# Interface.net
KiCad netlist of a schematic drawn in Altium Designer
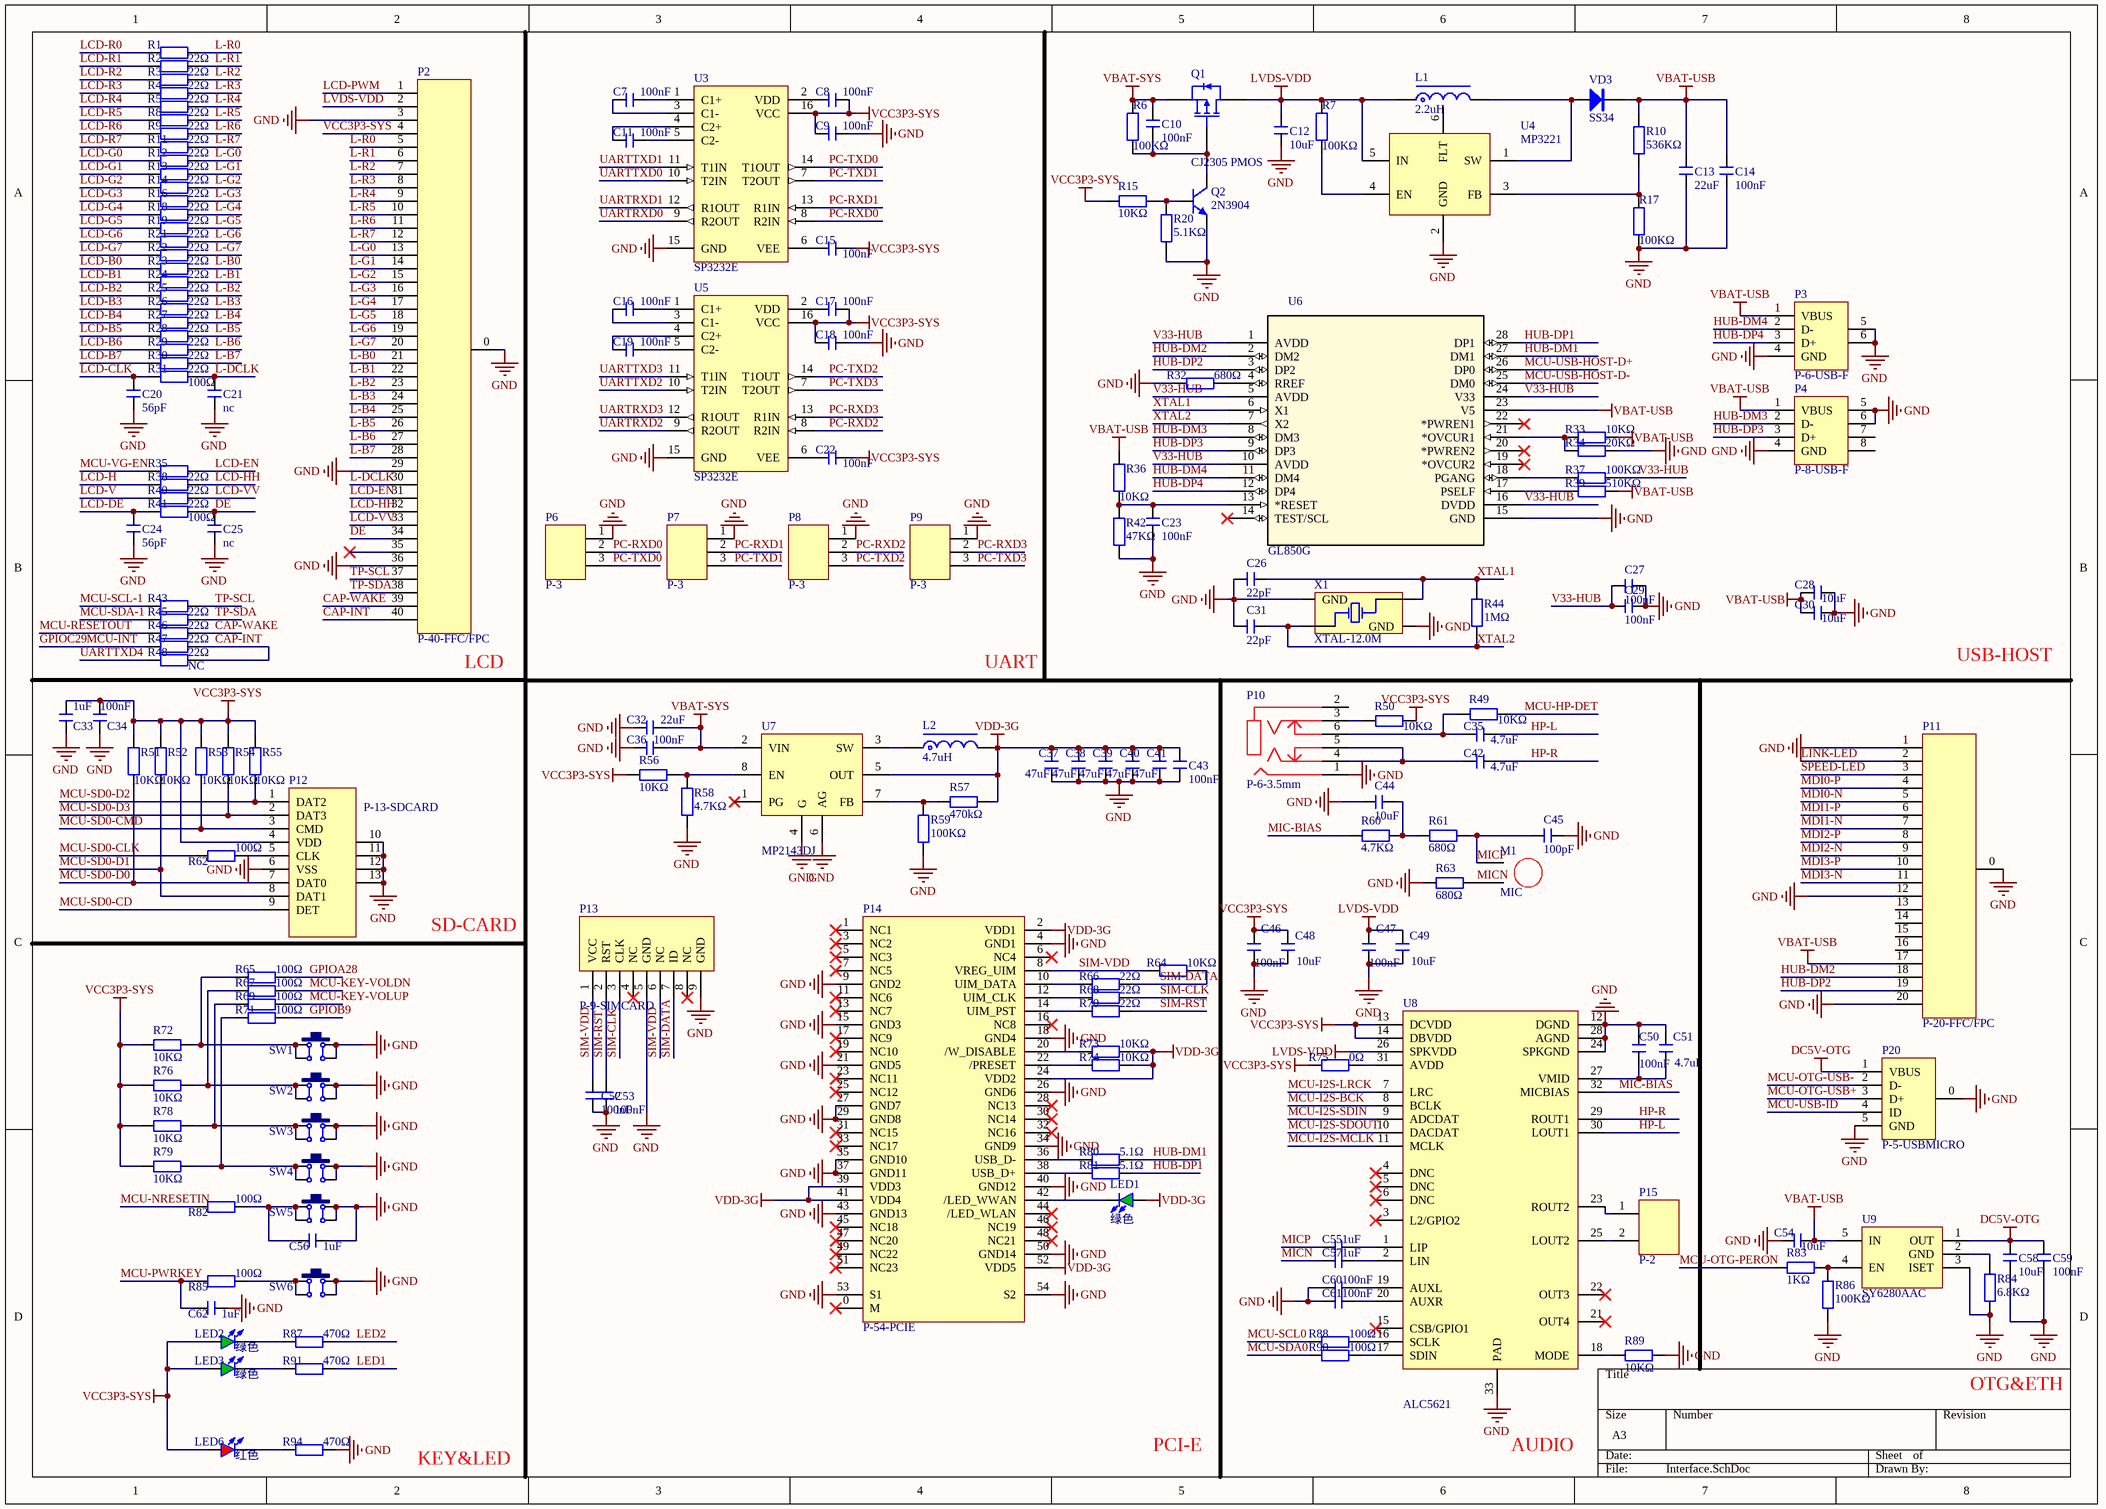
[diagram p0: Interface.SchDoc]

(export (version "E")
  (design (tool "Eeschema 10.0.6"))
  (components
    (comp (ref "C7")
      (value "100nF")
      (footprint "C 0402")
      (description "无极性贴片电容")
      (fields (field (name "版权归属") "源创客"))
      (libsource (lib "ZZF_Library") (part "C 100nF"))
    )
    (comp (ref "C8")
      (value "100nF")
      (footprint "C 0402")
      (description "无极性贴片电容")
      (fields (field (name "版权归属") "源创客"))
      (libsource (lib "ZZF_Library") (part "C 100nF"))
    )
    (comp (ref "C9")
      (value "100nF")
      (footprint "C 0402")
      (description "无极性贴片电容")
      (fields (field (name "版权归属") "源创客"))
      (libsource (lib "ZZF_Library") (part "C 100nF"))
    )
    (comp (ref "C10")
      (value "100nF")
      (footprint "C 0402")
      (description "无极性贴片电容")
      (fields (field (name "版权归属") "源创客"))
      (libsource (lib "ZZF_Library") (part "C 100nF"))
    )
    (comp (ref "C11")
      (value "100nF")
      (footprint "C 0402")
      (description "无极性贴片电容")
      (fields (field (name "版权归属") "源创客"))
      (libsource (lib "ZZF_Library") (part "C 100nF"))
    )
    (comp (ref "C12")
      (value "10uF")
      (footprint "C 0402")
      (description "无极性贴片电容")
      (fields (field (name "版权归属") "源创客"))
      (libsource (lib "ZZF_Library") (part "C 10uF"))
    )
    (comp (ref "C13")
      (value "22uF")
      (footprint "C 0805")
      (description "无极性贴片电容")
      (fields (field (name "版权归属") "源创客"))
      (libsource (lib "ZZF_Library") (part "C 22uF"))
    )
    (comp (ref "C14")
      (value "100nF")
      (footprint "C 0402")
      (description "无极性贴片电容")
      (fields (field (name "版权归属") "源创客"))
      (libsource (lib "ZZF_Library") (part "C 100nF"))
    )
    (comp (ref "C15")
      (value "100nF")
      (footprint "C 0402")
      (description "无极性贴片电容")
      (fields (field (name "版权归属") "源创客"))
      (libsource (lib "ZZF_Library") (part "C 100nF"))
    )
    (comp (ref "C16")
      (value "100nF")
      (footprint "C 0402")
      (description "无极性贴片电容")
      (fields (field (name "版权归属") "源创客"))
      (libsource (lib "ZZF_Library") (part "C 100nF"))
    )
    (comp (ref "C17")
      (value "100nF")
      (footprint "C 0402")
      (description "无极性贴片电容")
      (fields (field (name "版权归属") "源创客"))
      (libsource (lib "ZZF_Library") (part "C 100nF"))
    )
    (comp (ref "C18")
      (value "100nF")
      (footprint "C 0402")
      (description "无极性贴片电容")
      (fields (field (name "版权归属") "源创客"))
      (libsource (lib "ZZF_Library") (part "C 100nF"))
    )
    (comp (ref "C19")
      (value "100nF")
      (footprint "C 0402")
      (description "无极性贴片电容")
      (fields (field (name "版权归属") "源创客"))
      (libsource (lib "ZZF_Library") (part "C 100nF"))
    )
    (comp (ref "C20")
      (value "56pF")
      (footprint "C 0402")
      (description "无极性贴片电容")
      (fields (field (name "版权归属") "源创客"))
      (libsource (lib "ZZF_Library") (part "C 56pF"))
    )
    (comp (ref "C21")
      (value "nc")
      (footprint "C 0402")
      (description "无极性贴片电容")
      (fields (field (name "版权归属") "源创客"))
      (libsource (lib "ZZF_Library") (part "C 56pF"))
    )
    (comp (ref "C22")
      (value "100nF")
      (footprint "C 0402")
      (description "无极性贴片电容")
      (fields (field (name "版权归属") "源创客"))
      (libsource (lib "ZZF_Library") (part "C 100nF"))
    )
    (comp (ref "C23")
      (value "100nF")
      (footprint "C 0402")
      (description "无极性贴片电容")
      (fields (field (name "版权归属") "源创客"))
      (libsource (lib "ZZF_Library") (part "C 100nF"))
    )
    (comp (ref "C24")
      (value "56pF")
      (footprint "C 0402")
      (description "无极性贴片电容")
      (fields (field (name "版权归属") "源创客"))
      (libsource (lib "ZZF_Library") (part "C 56pF"))
    )
    (comp (ref "C25")
      (value "nc")
      (footprint "C 0402")
      (description "无极性贴片电容")
      (fields (field (name "版权归属") "源创客"))
      (libsource (lib "ZZF_Library") (part "C 56pF"))
    )
    (comp (ref "C26")
      (value "22pF")
      (footprint "C 0402")
      (description "无极性贴片电容")
      (fields (field (name "版权归属") "源创客"))
      (libsource (lib "ZZF_Library") (part "C 22pF"))
    )
    (comp (ref "C27")
      (value "100nF")
      (footprint "C 0402")
      (description "无极性贴片电容")
      (fields (field (name "版权归属") "源创客"))
      (libsource (lib "ZZF_Library") (part "C 100nF"))
    )
    (comp (ref "C28")
      (value "10uF")
      (footprint "C 0805")
      (description "无极性贴片电容")
      (fields (field (name "版权归属") "源创客"))
      (libsource (lib "ZZF_Library") (part "C 10uF"))
    )
    (comp (ref "C29")
      (value "100nF")
      (footprint "C 0402")
      (description "无极性贴片电容")
      (fields (field (name "版权归属") "源创客"))
      (libsource (lib "ZZF_Library") (part "C 100nF"))
    )
    (comp (ref "C30")
      (value "10uF")
      (footprint "C 0805")
      (description "无极性贴片电容")
      (fields (field (name "版权归属") "源创客"))
      (libsource (lib "ZZF_Library") (part "C 10uF"))
    )
    (comp (ref "C31")
      (value "22pF")
      (footprint "C 0402")
      (description "无极性贴片电容")
      (fields (field (name "版权归属") "源创客"))
      (libsource (lib "ZZF_Library") (part "C 22pF"))
    )
    (comp (ref "C32")
      (value "22uF")
      (footprint "C 0805")
      (description "无极性贴片电容")
      (fields (field (name "版权归属") "源创客"))
      (libsource (lib "ZZF_Library") (part "C 22uF"))
    )
    (comp (ref "C33")
      (value "1uF")
      (footprint "C 0402")
      (description "无极性贴片电容")
      (fields (field (name "版权归属") "源创客"))
      (libsource (lib "ZZF_Library") (part "C 1uF"))
    )
    (comp (ref "C34")
      (value "100nF")
      (footprint "C 0402")
      (description "无极性贴片电容")
      (fields (field (name "版权归属") "源创客"))
      (libsource (lib "ZZF_Library") (part "C 100nF"))
    )
    (comp (ref "C35")
      (value "4.7uF")
      (footprint "C 0402")
      (description "无极性贴片电容")
      (fields (field (name "版权归属") "源创客"))
      (libsource (lib "ZZF_Library") (part "C 4.7uF"))
    )
    (comp (ref "C36")
      (value "100nF")
      (footprint "C 0402")
      (description "无极性贴片电容")
      (fields (field (name "版权归属") "源创客"))
      (libsource (lib "ZZF_Library") (part "C 100nF"))
    )
    (comp (ref "C37")
      (value "47uF")
      (footprint "C 1206")
      (description "无极性贴片电容")
      (fields (field (name "版权归属") "源创客"))
      (libsource (lib "ZZF_Library") (part "C 22uF"))
    )
    (comp (ref "C38")
      (value "47uF")
      (footprint "C 1206")
      (description "无极性贴片电容")
      (fields (field (name "版权归属") "源创客"))
      (libsource (lib "ZZF_Library") (part "C 22uF"))
    )
    (comp (ref "C39")
      (value "47uF")
      (footprint "C 1206")
      (description "无极性贴片电容")
      (fields (field (name "版权归属") "源创客"))
      (libsource (lib "ZZF_Library") (part "C 22uF"))
    )
    (comp (ref "C40")
      (value "47uF")
      (footprint "C 1206")
      (description "无极性贴片电容")
      (fields (field (name "版权归属") "源创客"))
      (libsource (lib "ZZF_Library") (part "C 22uF"))
    )
    (comp (ref "C41")
      (value "47uF")
      (footprint "C 1206")
      (description "无极性贴片电容")
      (fields (field (name "版权归属") "源创客"))
      (libsource (lib "ZZF_Library") (part "C 22uF"))
    )
    (comp (ref "C42")
      (value "4.7uF")
      (footprint "C 0402")
      (description "无极性贴片电容")
      (fields (field (name "版权归属") "源创客"))
      (libsource (lib "ZZF_Library") (part "C 4.7uF"))
    )
    (comp (ref "C43")
      (value "100nF")
      (footprint "C 0402")
      (description "无极性贴片电容")
      (fields (field (name "版权归属") "源创客"))
      (libsource (lib "ZZF_Library") (part "C 100nF"))
    )
    (comp (ref "C44")
      (value "10uF")
      (footprint "C 0402")
      (description "无极性贴片电容")
      (fields (field (name "版权归属") "源创客"))
      (libsource (lib "ZZF_Library") (part "C 10uF"))
    )
    (comp (ref "C45")
      (value "100pF")
      (footprint "C 0402")
      (description "无极性贴片电容")
      (fields (field (name "版权归属") "源创客"))
      (libsource (lib "ZZF_Library") (part "C 100pF"))
    )
    (comp (ref "C46")
      (value "100nF")
      (footprint "C 0402")
      (description "无极性贴片电容")
      (fields (field (name "版权归属") "源创客"))
      (libsource (lib "ZZF_Library") (part "C 100nF"))
    )
    (comp (ref "C47")
      (value "100nF")
      (footprint "C 0402")
      (description "无极性贴片电容")
      (fields (field (name "版权归属") "源创客"))
      (libsource (lib "ZZF_Library") (part "C 100nF"))
    )
    (comp (ref "C48")
      (value "10uF")
      (footprint "C 0402")
      (description "无极性贴片电容")
      (fields (field (name "版权归属") "源创客"))
      (libsource (lib "ZZF_Library") (part "C 10uF"))
    )
    (comp (ref "C49")
      (value "10uF")
      (footprint "C 0402")
      (description "无极性贴片电容")
      (fields (field (name "版权归属") "源创客"))
      (libsource (lib "ZZF_Library") (part "C 10uF"))
    )
    (comp (ref "C50")
      (value "100nF")
      (footprint "C 0402")
      (description "无极性贴片电容")
      (fields (field (name "版权归属") "源创客"))
      (libsource (lib "ZZF_Library") (part "C 100nF"))
    )
    (comp (ref "C51")
      (value "4.7uF")
      (footprint "C 0402")
      (description "无极性贴片电容")
      (fields (field (name "版权归属") "源创客"))
      (libsource (lib "ZZF_Library") (part "C 4.7uF"))
    )
    (comp (ref "C52")
      (value "100nF")
      (footprint "C 0402")
      (description "无极性贴片电容")
      (fields (field (name "版权归属") "源创客"))
      (libsource (lib "ZZF_Library") (part "C 100nF"))
    )
    (comp (ref "C53")
      (value "100nF")
      (footprint "C 0402")
      (description "无极性贴片电容")
      (fields (field (name "版权归属") "源创客"))
      (libsource (lib "ZZF_Library") (part "C 100nF"))
    )
    (comp (ref "C54")
      (value "10uF")
      (footprint "C 0805")
      (description "无极性贴片电容")
      (fields (field (name "版权归属") "源创客"))
      (libsource (lib "ZZF_Library") (part "C 10uF"))
    )
    (comp (ref "C55")
      (value "1uF")
      (footprint "C 0402")
      (description "无极性贴片电容")
      (fields (field (name "版权归属") "源创客"))
      (libsource (lib "ZZF_Library") (part "C 1uF"))
    )
    (comp (ref "C56")
      (value "1uF")
      (footprint "C 0402")
      (description "无极性贴片电容")
      (fields (field (name "版权归属") "源创客"))
      (libsource (lib "ZZF_Library") (part "C 1uF"))
    )
    (comp (ref "C57")
      (value "1uF")
      (footprint "C 0402")
      (description "无极性贴片电容")
      (fields (field (name "版权归属") "源创客"))
      (libsource (lib "ZZF_Library") (part "C 1uF"))
    )
    (comp (ref "C58")
      (value "10uF")
      (footprint "C 0805")
      (description "无极性贴片电容")
      (fields (field (name "版权归属") "源创客"))
      (libsource (lib "ZZF_Library") (part "C 10uF"))
    )
    (comp (ref "C59")
      (value "100nF")
      (footprint "C 0402")
      (description "无极性贴片电容")
      (fields (field (name "版权归属") "源创客"))
      (libsource (lib "ZZF_Library") (part "C 100nF"))
    )
    (comp (ref "C60")
      (value "100nF")
      (footprint "C 0402")
      (description "无极性贴片电容")
      (fields (field (name "版权归属") "源创客"))
      (libsource (lib "ZZF_Library") (part "C 100nF"))
    )
    (comp (ref "C61")
      (value "100nF")
      (footprint "C 0402")
      (description "无极性贴片电容")
      (fields (field (name "版权归属") "源创客"))
      (libsource (lib "ZZF_Library") (part "C 100nF"))
    )
    (comp (ref "C62")
      (value "1uF")
      (footprint "C 0402")
      (description "无极性贴片电容")
      (fields (field (name "版权归属") "源创客"))
      (libsource (lib "ZZF_Library") (part "C 1uF"))
    )
    (comp (ref "L1")
      (value "2.2uH")
      (footprint "L CD54")
      (description "贴片功率电感")
      (fields (field (name "版权归属") "源创客"))
      (libsource (lib "ZZF_Library") (part "L-CD  3.3uH"))
    )
    (comp (ref "L2")
      (value "4.7uH")
      (footprint "L CD54")
      (description "贴片功率电感")
      (fields (field (name "版权归属") "源创客"))
      (libsource (lib "ZZF_Library") (part "L-CD  3.3uH"))
    )
    (comp (ref "LED1")
      (value "绿色")
      (footprint "LED 0805G")
      (description "贴片LED")
      (fields (field (name "版权归属") "源创客"))
      (libsource (lib "ZZF_Library") (part "LED SMD-GREEN"))
    )
    (comp (ref "LED2")
      (value "绿色")
      (footprint "LED 0603G")
      (description "贴片LED")
      (fields (field (name "版权归属") "源创客"))
      (libsource (lib "ZZF_Library") (part "LED SMD-GREEN"))
    )
    (comp (ref "LED3")
      (value "绿色")
      (footprint "LED 0603G")
      (description "贴片LED")
      (fields (field (name "版权归属") "源创客"))
      (libsource (lib "ZZF_Library") (part "LED SMD-GREEN"))
    )
    (comp (ref "LED6")
      (value "红色")
      (footprint "LED 0603R")
      (description "贴片LED")
      (fields (field (name "版权归属") "源创客"))
      (libsource (lib "ZZF_Library") (part "LED SMD-RED"))
    )
    (comp (ref "M1")
      (value "MIC")
      (footprint "MIC")
      (description "耳麦")
      (libsource (lib "ZZF_Library") (part "MIC"))
    )
    (comp (ref "P2")
      (value "P-40-FFC/FPC")
      (footprint "P FFC/FPC-40")
      (description "40脚FFC/PFC接口")
      (libsource (lib "ZZF_Library") (part "P-40-FFC/PFC"))
    )
    (comp (ref "P3")
      (value "P-6-USB-F")
      (footprint "P USB-A")
      (description "卧式USB母头")
      (libsource (lib "ZZF_Library") (part "P-6-USB-F"))
    )
    (comp (ref "P4")
      (value "P-8-USB-F")
      (footprint "P USB2.0-4H4")
      (description "立式USB母头")
      (libsource (lib "ZZF_Library") (part "P-8-USB-F"))
    )
    (comp (ref "P6")
      (value "P-3")
      (footprint "P XH2.54-3")
      (description "3脚接插件")
      (libsource (lib "ZZF_Library") (part "P-3"))
    )
    (comp (ref "P7")
      (value "P-3")
      (footprint "P XH2.54-3")
      (description "3脚接插件")
      (libsource (lib "ZZF_Library") (part "P-3"))
    )
    (comp (ref "P8")
      (value "P-3")
      (footprint "P XH2.54-3")
      (description "3脚接插件")
      (libsource (lib "ZZF_Library") (part "P-3"))
    )
    (comp (ref "P9")
      (value "P-3")
      (footprint "P XH2.54-3")
      (description "3脚接插件")
      (libsource (lib "ZZF_Library") (part "P-3"))
    )
    (comp (ref "P10")
      (value "P-6-3.5mm")
      (footprint "P 3.5mm音频座")
      (description "耳机座")
      (libsource (lib "ZZF_Library") (part "P-6-3.5mm"))
    )
    (comp (ref "P11")
      (value "P-20-FFC/FPC")
      (footprint "P FFC/FPC-20")
      (description "20脚FFC/PFC接口")
      (libsource (lib "ZZF_Library") (part "P-20-FFC/PFC"))
    )
    (comp (ref "P12")
      (value "P-13-SDCARD")
      (footprint "P TFCARD")
      (description "SD卡")
      (libsource (lib "ZZF_Library") (part "P-13-SDCARD"))
    )
    (comp (ref "P13")
      (value "P-9-SIMCARD")
      (footprint "P SIMCARD")
      (description "SIM卡插槽")
      (libsource (lib "ZZF_Library") (part "P-9-SIMCARD"))
    )
    (comp (ref "P14")
      (value "P-54-PCIE")
      (footprint "P PCIE54-AB")
      (description "PCIE接口")
      (libsource (lib "ZZF_Library") (part "P-54-PCIE"))
    )
    (comp (ref "P15")
      (value "P-2")
      (footprint "P XH2.54-2")
      (description "2脚接插件")
      (libsource (lib "ZZF_Library") (part "P-2"))
    )
    (comp (ref "P20")
      (value "P-5-USBMICRO")
      (footprint "P USB-MICRO2")
      (description "USBMICRO")
      (libsource (lib "ZZF_Library") (part "P-5-USBMICRO"))
    )
    (comp (ref "Q1")
      (value "CJ2305 PMOS")
      (footprint "SC SOT23-3M")
      (description "MOS管")
      (libsource (lib "ZZF_Library") (part "CJ2305 PMOS"))
    )
    (comp (ref "Q2")
      (value "2N3904")
      (footprint "SC SOT23-3M")
      (description "低频放大-NPN型")
      (fields (field (name "版权归属") "源创客"))
      (libsource (lib "ZZF_Library") (part "S9013"))
    )
    (comp (ref "R1")
      (value "22Ω")
      (footprint "R 0402")
      (description "贴片电阻")
      (fields (field (name "版权归属") "源创客"))
      (libsource (lib "ZZF_Library") (part "R 22Ω"))
    )
    (comp (ref "R2")
      (value "22Ω")
      (footprint "R 0402")
      (description "贴片电阻")
      (fields (field (name "版权归属") "源创客"))
      (libsource (lib "ZZF_Library") (part "R 22Ω"))
    )
    (comp (ref "R3")
      (value "22Ω")
      (footprint "R 0402")
      (description "贴片电阻")
      (fields (field (name "版权归属") "源创客"))
      (libsource (lib "ZZF_Library") (part "R 22Ω"))
    )
    (comp (ref "R4")
      (value "22Ω")
      (footprint "R 0402")
      (description "贴片电阻")
      (fields (field (name "版权归属") "源创客"))
      (libsource (lib "ZZF_Library") (part "R 22Ω"))
    )
    (comp (ref "R5")
      (value "22Ω")
      (footprint "R 0402")
      (description "贴片电阻")
      (fields (field (name "版权归属") "源创客"))
      (libsource (lib "ZZF_Library") (part "R 22Ω"))
    )
    (comp (ref "R6")
      (value "100KΩ")
      (footprint "R 0402")
      (description "贴片电阻")
      (fields (field (name "版权归属") "源创客"))
      (libsource (lib "ZZF_Library") (part "R 100KΩ"))
    )
    (comp (ref "R7")
      (value "100KΩ")
      (footprint "R 0402")
      (description "贴片电阻")
      (fields (field (name "版权归属") "源创客"))
      (libsource (lib "ZZF_Library") (part "R 100KΩ"))
    )
    (comp (ref "R8")
      (value "22Ω")
      (footprint "R 0402")
      (description "贴片电阻")
      (fields (field (name "版权归属") "源创客"))
      (libsource (lib "ZZF_Library") (part "R 22Ω"))
    )
    (comp (ref "R9")
      (value "22Ω")
      (footprint "R 0402")
      (description "贴片电阻")
      (fields (field (name "版权归属") "源创客"))
      (libsource (lib "ZZF_Library") (part "R 22Ω"))
    )
    (comp (ref "R10")
      (value "536KΩ")
      (footprint "R 0402-HP")
      (description "贴片电阻")
      (fields (field (name "版权归属") "源创客"))
      (libsource (lib "ZZF_Library") (part "R 536KΩ"))
    )
    (comp (ref "R11")
      (value "22Ω")
      (footprint "R 0402")
      (description "贴片电阻")
      (fields (field (name "版权归属") "源创客"))
      (libsource (lib "ZZF_Library") (part "R 22Ω"))
    )
    (comp (ref "R12")
      (value "22Ω")
      (footprint "R 0402")
      (description "贴片电阻")
      (fields (field (name "版权归属") "源创客"))
      (libsource (lib "ZZF_Library") (part "R 22Ω"))
    )
    (comp (ref "R13")
      (value "22Ω")
      (footprint "R 0402")
      (description "贴片电阻")
      (fields (field (name "版权归属") "源创客"))
      (libsource (lib "ZZF_Library") (part "R 22Ω"))
    )
    (comp (ref "R14")
      (value "22Ω")
      (footprint "R 0402")
      (description "贴片电阻")
      (fields (field (name "版权归属") "源创客"))
      (libsource (lib "ZZF_Library") (part "R 22Ω"))
    )
    (comp (ref "R15")
      (value "10KΩ")
      (footprint "R 0402")
      (description "贴片电阻")
      (fields (field (name "版权归属") "源创客"))
      (libsource (lib "ZZF_Library") (part "R 10KΩ"))
    )
    (comp (ref "R16")
      (value "22Ω")
      (footprint "R 0402")
      (description "贴片电阻")
      (fields (field (name "版权归属") "源创客"))
      (libsource (lib "ZZF_Library") (part "R 22Ω"))
    )
    (comp (ref "R17")
      (value "100KΩ")
      (footprint "R 0402-HP")
      (description "贴片电阻")
      (fields (field (name "版权归属") "源创客"))
      (libsource (lib "ZZF_Library") (part "R 100KΩ"))
    )
    (comp (ref "R18")
      (value "22Ω")
      (footprint "R 0402")
      (description "贴片电阻")
      (fields (field (name "版权归属") "源创客"))
      (libsource (lib "ZZF_Library") (part "R 22Ω"))
    )
    (comp (ref "R19")
      (value "22Ω")
      (footprint "R 0402")
      (description "贴片电阻")
      (fields (field (name "版权归属") "源创客"))
      (libsource (lib "ZZF_Library") (part "R 22Ω"))
    )
    (comp (ref "R20")
      (value "5.1KΩ")
      (footprint "R 0402")
      (description "贴片电阻")
      (fields (field (name "版权归属") "源创客"))
      (libsource (lib "ZZF_Library") (part "R 5.1KΩ"))
    )
    (comp (ref "R21")
      (value "22Ω")
      (footprint "R 0402")
      (description "贴片电阻")
      (fields (field (name "版权归属") "源创客"))
      (libsource (lib "ZZF_Library") (part "R 22Ω"))
    )
    (comp (ref "R22")
      (value "22Ω")
      (footprint "R 0402")
      (description "贴片电阻")
      (fields (field (name "版权归属") "源创客"))
      (libsource (lib "ZZF_Library") (part "R 22Ω"))
    )
    (comp (ref "R23")
      (value "22Ω")
      (footprint "R 0402")
      (description "贴片电阻")
      (fields (field (name "版权归属") "源创客"))
      (libsource (lib "ZZF_Library") (part "R 22Ω"))
    )
    (comp (ref "R24")
      (value "22Ω")
      (footprint "R 0402")
      (description "贴片电阻")
      (fields (field (name "版权归属") "源创客"))
      (libsource (lib "ZZF_Library") (part "R 22Ω"))
    )
    (comp (ref "R25")
      (value "22Ω")
      (footprint "R 0402")
      (description "贴片电阻")
      (fields (field (name "版权归属") "源创客"))
      (libsource (lib "ZZF_Library") (part "R 22Ω"))
    )
    (comp (ref "R26")
      (value "22Ω")
      (footprint "R 0402")
      (description "贴片电阻")
      (fields (field (name "版权归属") "源创客"))
      (libsource (lib "ZZF_Library") (part "R 22Ω"))
    )
    (comp (ref "R27")
      (value "22Ω")
      (footprint "R 0402")
      (description "贴片电阻")
      (fields (field (name "版权归属") "源创客"))
      (libsource (lib "ZZF_Library") (part "R 22Ω"))
    )
    (comp (ref "R28")
      (value "22Ω")
      (footprint "R 0402")
      (description "贴片电阻")
      (fields (field (name "版权归属") "源创客"))
      (libsource (lib "ZZF_Library") (part "R 22Ω"))
    )
    (comp (ref "R29")
      (value "22Ω")
      (footprint "R 0402")
      (description "贴片电阻")
      (fields (field (name "版权归属") "源创客"))
      (libsource (lib "ZZF_Library") (part "R 22Ω"))
    )
    (comp (ref "R30")
      (value "22Ω")
      (footprint "R 0402")
      (description "贴片电阻")
      (fields (field (name "版权归属") "源创客"))
      (libsource (lib "ZZF_Library") (part "R 22Ω"))
    )
    (comp (ref "R31")
      (value "100Ω")
      (footprint "R 0402")
      (description "贴片电阻")
      (fields (field (name "版权归属") "源创客"))
      (libsource (lib "ZZF_Library") (part "R 100Ω"))
    )
    (comp (ref "R32")
      (value "680Ω")
      (footprint "R 0402-HP")
      (description "贴片电阻")
      (fields (field (name "版权归属") "源创客"))
      (libsource (lib "ZZF_Library") (part "R 680Ω"))
    )
    (comp (ref "R33")
      (value "10KΩ")
      (footprint "R 0402")
      (description "贴片电阻")
      (fields (field (name "版权归属") "源创客"))
      (libsource (lib "ZZF_Library") (part "R 10KΩ"))
    )
    (comp (ref "R34")
      (value "20KΩ")
      (footprint "R 0402")
      (description "贴片电阻")
      (fields (field (name "版权归属") "源创客"))
      (libsource (lib "ZZF_Library") (part "R 20KΩ"))
    )
    (comp (ref "R35")
      (value "22Ω")
      (footprint "R 0402")
      (description "贴片电阻")
      (fields (field (name "版权归属") "源创客"))
      (libsource (lib "ZZF_Library") (part "R 22Ω"))
    )
    (comp (ref "R36")
      (value "10KΩ")
      (footprint "R 0402")
      (description "贴片电阻")
      (fields (field (name "版权归属") "源创客"))
      (libsource (lib "ZZF_Library") (part "R 10KΩ"))
    )
    (comp (ref "R37")
      (value "100KΩ")
      (footprint "R 0402")
      (description "贴片电阻")
      (fields (field (name "版权归属") "源创客"))
      (libsource (lib "ZZF_Library") (part "R 100KΩ"))
    )
    (comp (ref "R38")
      (value "22Ω")
      (footprint "R 0402")
      (description "贴片电阻")
      (fields (field (name "版权归属") "源创客"))
      (libsource (lib "ZZF_Library") (part "R 22Ω"))
    )
    (comp (ref "R39")
      (value "510KΩ")
      (footprint "R 0402")
      (description "贴片电阻")
      (fields (field (name "版权归属") "源创客"))
      (libsource (lib "ZZF_Library") (part "R 510KΩ"))
    )
    (comp (ref "R40")
      (value "22Ω")
      (footprint "R 0402")
      (description "贴片电阻")
      (fields (field (name "版权归属") "源创客"))
      (libsource (lib "ZZF_Library") (part "R 22Ω"))
    )
    (comp (ref "R41")
      (value "100Ω")
      (footprint "R 0402")
      (description "贴片电阻")
      (fields (field (name "版权归属") "源创客"))
      (libsource (lib "ZZF_Library") (part "R 100Ω"))
    )
    (comp (ref "R42")
      (value "47KΩ")
      (footprint "R 0402")
      (description "贴片电阻")
      (fields (field (name "版权归属") "源创客"))
      (libsource (lib "ZZF_Library") (part "R 47KΩ"))
    )
    (comp (ref "R43")
      (value "22Ω")
      (footprint "R 0402")
      (description "贴片电阻")
      (fields (field (name "版权归属") "源创客"))
      (libsource (lib "ZZF_Library") (part "R 22Ω"))
    )
    (comp (ref "R44")
      (value "1MΩ")
      (footprint "R 0402")
      (description "贴片电阻")
      (fields (field (name "版权归属") "源创客"))
      (libsource (lib "ZZF_Library") (part "R 1MΩ"))
    )
    (comp (ref "R45")
      (value "22Ω")
      (footprint "R 0402")
      (description "贴片电阻")
      (fields (field (name "版权归属") "源创客"))
      (libsource (lib "ZZF_Library") (part "R 22Ω"))
    )
    (comp (ref "R46")
      (value "22Ω")
      (footprint "R 0402")
      (description "贴片电阻")
      (fields (field (name "版权归属") "源创客"))
      (libsource (lib "ZZF_Library") (part "R 22Ω"))
    )
    (comp (ref "R47")
      (value "22Ω")
      (footprint "R 0402")
      (description "贴片电阻")
      (fields (field (name "版权归属") "源创客"))
      (libsource (lib "ZZF_Library") (part "R 22Ω"))
    )
    (comp (ref "R48")
      (value "NC")
      (footprint "R 0402")
      (description "贴片电阻")
      (fields (field (name "版权归属") "源创客"))
      (libsource (lib "ZZF_Library") (part "R 22Ω"))
    )
    (comp (ref "R49")
      (value "10KΩ")
      (footprint "R 0402")
      (description "贴片电阻")
      (fields (field (name "版权归属") "源创客"))
      (libsource (lib "ZZF_Library") (part "R 10KΩ"))
    )
    (comp (ref "R50")
      (value "10KΩ")
      (footprint "R 0402")
      (description "贴片电阻")
      (fields (field (name "版权归属") "源创客"))
      (libsource (lib "ZZF_Library") (part "R 10KΩ"))
    )
    (comp (ref "R51")
      (value "10KΩ")
      (footprint "R 0402")
      (description "贴片电阻")
      (fields (field (name "版权归属") "源创客"))
      (libsource (lib "ZZF_Library") (part "R 10KΩ"))
    )
    (comp (ref "R52")
      (value "10KΩ")
      (footprint "R 0402")
      (description "贴片电阻")
      (fields (field (name "版权归属") "源创客"))
      (libsource (lib "ZZF_Library") (part "R 10KΩ"))
    )
    (comp (ref "R53")
      (value "10KΩ")
      (footprint "R 0402")
      (description "贴片电阻")
      (fields (field (name "版权归属") "源创客"))
      (libsource (lib "ZZF_Library") (part "R 10KΩ"))
    )
    (comp (ref "R54")
      (value "10KΩ")
      (footprint "R 0402")
      (description "贴片电阻")
      (fields (field (name "版权归属") "源创客"))
      (libsource (lib "ZZF_Library") (part "R 10KΩ"))
    )
    (comp (ref "R55")
      (value "10KΩ")
      (footprint "R 0402")
      (description "贴片电阻")
      (fields (field (name "版权归属") "源创客"))
      (libsource (lib "ZZF_Library") (part "R 10KΩ"))
    )
    (comp (ref "R56")
      (value "10KΩ")
      (footprint "R 0402")
      (description "贴片电阻")
      (fields (field (name "版权归属") "源创客"))
      (libsource (lib "ZZF_Library") (part "R 10KΩ"))
    )
    (comp (ref "R57")
      (value "470kΩ")
      (footprint "R 0402-HP")
      (description "贴片电阻")
      (fields (field (name "版权归属") "源创客"))
      (libsource (lib "ZZF_Library") (part "R 470Ω"))
    )
    (comp (ref "R58")
      (value "4.7KΩ")
      (footprint "R 0402")
      (description "贴片电阻")
      (fields (field (name "版权归属") "源创客"))
      (libsource (lib "ZZF_Library") (part "R 4.7KΩ"))
    )
    (comp (ref "R59")
      (value "100KΩ")
      (footprint "R 0402-HP")
      (description "贴片电阻")
      (fields (field (name "版权归属") "源创客"))
      (libsource (lib "ZZF_Library") (part "R 100KΩ"))
    )
    (comp (ref "R60")
      (value "4.7KΩ")
      (footprint "R 0402")
      (description "贴片电阻")
      (fields (field (name "版权归属") "源创客"))
      (libsource (lib "ZZF_Library") (part "R 4.7KΩ"))
    )
    (comp (ref "R61")
      (value "680Ω")
      (footprint "R 0402")
      (description "贴片电阻")
      (fields (field (name "版权归属") "源创客"))
      (libsource (lib "ZZF_Library") (part "R 680Ω"))
    )
    (comp (ref "R62")
      (value "100Ω")
      (footprint "R 0402")
      (description "贴片电阻")
      (fields (field (name "版权归属") "源创客"))
      (libsource (lib "ZZF_Library") (part "R 100Ω"))
    )
    (comp (ref "R63")
      (value "680Ω")
      (footprint "R 0402")
      (description "贴片电阻")
      (fields (field (name "版权归属") "源创客"))
      (libsource (lib "ZZF_Library") (part "R 680Ω"))
    )
    (comp (ref "R64")
      (value "10KΩ")
      (footprint "R 0402")
      (description "贴片电阻")
      (fields (field (name "版权归属") "源创客"))
      (libsource (lib "ZZF_Library") (part "R 10KΩ"))
    )
    (comp (ref "R65")
      (value "100Ω")
      (footprint "R 0402")
      (description "贴片电阻")
      (fields (field (name "版权归属") "源创客"))
      (libsource (lib "ZZF_Library") (part "R 100Ω"))
    )
    (comp (ref "R66")
      (value "22Ω")
      (footprint "R 0402")
      (description "贴片电阻")
      (fields (field (name "版权归属") "源创客"))
      (libsource (lib "ZZF_Library") (part "R 22Ω"))
    )
    (comp (ref "R67")
      (value "100Ω")
      (footprint "R 0402")
      (description "贴片电阻")
      (fields (field (name "版权归属") "源创客"))
      (libsource (lib "ZZF_Library") (part "R 100Ω"))
    )
    (comp (ref "R68")
      (value "22Ω")
      (footprint "R 0402")
      (description "贴片电阻")
      (fields (field (name "版权归属") "源创客"))
      (libsource (lib "ZZF_Library") (part "R 22Ω"))
    )
    (comp (ref "R69")
      (value "100Ω")
      (footprint "R 0402")
      (description "贴片电阻")
      (fields (field (name "版权归属") "源创客"))
      (libsource (lib "ZZF_Library") (part "R 100Ω"))
    )
    (comp (ref "R70")
      (value "22Ω")
      (footprint "R 0402")
      (description "贴片电阻")
      (fields (field (name "版权归属") "源创客"))
      (libsource (lib "ZZF_Library") (part "R 22Ω"))
    )
    (comp (ref "R71")
      (value "100Ω")
      (footprint "R 0402")
      (description "贴片电阻")
      (fields (field (name "版权归属") "源创客"))
      (libsource (lib "ZZF_Library") (part "R 100Ω"))
    )
    (comp (ref "R72")
      (value "10KΩ")
      (footprint "R 0402")
      (description "贴片电阻")
      (fields (field (name "版权归属") "源创客"))
      (libsource (lib "ZZF_Library") (part "R 10KΩ"))
    )
    (comp (ref "R73")
      (value "10KΩ")
      (footprint "R 0402")
      (description "贴片电阻")
      (fields (field (name "版权归属") "源创客"))
      (libsource (lib "ZZF_Library") (part "R 10KΩ"))
    )
    (comp (ref "R74")
      (value "10KΩ")
      (footprint "R 0402")
      (description "贴片电阻")
      (fields (field (name "版权归属") "源创客"))
      (libsource (lib "ZZF_Library") (part "R 10KΩ"))
    )
    (comp (ref "R75")
      (value "0Ω")
      (footprint "R 0402")
      (description "贴片电阻")
      (fields (field (name "版权归属") "源创客"))
      (libsource (lib "ZZF_Library") (part "R 0Ω"))
    )
    (comp (ref "R76")
      (value "10KΩ")
      (footprint "R 0402")
      (description "贴片电阻")
      (fields (field (name "版权归属") "源创客"))
      (libsource (lib "ZZF_Library") (part "R 10KΩ"))
    )
    (comp (ref "R78")
      (value "10KΩ")
      (footprint "R 0402")
      (description "贴片电阻")
      (fields (field (name "版权归属") "源创客"))
      (libsource (lib "ZZF_Library") (part "R 10KΩ"))
    )
    (comp (ref "R79")
      (value "10KΩ")
      (footprint "R 0402")
      (description "贴片电阻")
      (fields (field (name "版权归属") "源创客"))
      (libsource (lib "ZZF_Library") (part "R 10KΩ"))
    )
    (comp (ref "R80")
      (value "5.1Ω")
      (footprint "R 0402")
      (description "贴片电阻")
      (fields (field (name "版权归属") "源创客"))
      (libsource (lib "ZZF_Library") (part "R 5.1Ω"))
    )
    (comp (ref "R81")
      (value "5.1Ω")
      (footprint "R 0402")
      (description "贴片电阻")
      (fields (field (name "版权归属") "源创客"))
      (libsource (lib "ZZF_Library") (part "R 5.1Ω"))
    )
    (comp (ref "R82")
      (value "100Ω")
      (footprint "R 0402")
      (description "贴片电阻")
      (fields (field (name "版权归属") "源创客"))
      (libsource (lib "ZZF_Library") (part "R 100Ω"))
    )
    (comp (ref "R83")
      (value "1KΩ")
      (footprint "R 0402")
      (description "贴片电阻")
      (fields (field (name "版权归属") "源创客"))
      (libsource (lib "ZZF_Library") (part "R 1KΩ"))
    )
    (comp (ref "R84")
      (value "6.8KΩ")
      (footprint "R 0402")
      (description "贴片电阻")
      (fields (field (name "版权归属") "源创客"))
      (libsource (lib "ZZF_Library") (part "R 6.8KΩ"))
    )
    (comp (ref "R85")
      (value "100Ω")
      (footprint "R 0402")
      (description "贴片电阻")
      (fields (field (name "版权归属") "源创客"))
      (libsource (lib "ZZF_Library") (part "R 100Ω"))
    )
    (comp (ref "R86")
      (value "100KΩ")
      (footprint "R 0402")
      (description "贴片电阻")
      (fields (field (name "版权归属") "源创客"))
      (libsource (lib "ZZF_Library") (part "R 100KΩ"))
    )
    (comp (ref "R87")
      (value "470Ω")
      (footprint "R 0402")
      (description "贴片电阻")
      (fields (field (name "版权归属") "源创客"))
      (libsource (lib "ZZF_Library") (part "R 470Ω"))
    )
    (comp (ref "R88")
      (value "100Ω")
      (footprint "R 0402")
      (description "贴片电阻")
      (fields (field (name "版权归属") "源创客"))
      (libsource (lib "ZZF_Library") (part "R 100Ω"))
    )
    (comp (ref "R89")
      (value "10KΩ")
      (footprint "R 0402")
      (description "贴片电阻")
      (fields (field (name "版权归属") "源创客"))
      (libsource (lib "ZZF_Library") (part "R 10KΩ"))
    )
    (comp (ref "R90")
      (value "100Ω")
      (footprint "R 0402")
      (description "贴片电阻")
      (fields (field (name "版权归属") "源创客"))
      (libsource (lib "ZZF_Library") (part "R 100Ω"))
    )
    (comp (ref "R91")
      (value "470Ω")
      (footprint "R 0402")
      (description "贴片电阻")
      (fields (field (name "版权归属") "源创客"))
      (libsource (lib "ZZF_Library") (part "R 470Ω"))
    )
    (comp (ref "R94")
      (value "470Ω")
      (footprint "R 0402")
      (description "贴片电阻")
      (fields (field (name "版权归属") "源创客"))
      (libsource (lib "ZZF_Library") (part "R 470Ω"))
    )
    (comp (ref "SW1")
      (value "6x6x5")
      (footprint "KS TSW-SMD-6*6*4.3")
      (description "贴片6x6轻触开关")
      (fields (field (name "版权归属") "源创客"))
      (libsource (lib "ZZF_Library") (part "KS  TSW SMD-6x6"))
    )
    (comp (ref "SW2")
      (value "6x6x5")
      (footprint "KS TSW-SMD-6*6*4.3")
      (description "贴片6x6轻触开关")
      (fields (field (name "版权归属") "源创客"))
      (libsource (lib "ZZF_Library") (part "KS  TSW SMD-6x6"))
    )
    (comp (ref "SW3")
      (value "6x6x5")
      (footprint "KS TSW-SMD-6*6*4.3")
      (description "贴片6x6轻触开关")
      (fields (field (name "版权归属") "源创客"))
      (libsource (lib "ZZF_Library") (part "KS  TSW SMD-6x6"))
    )
    (comp (ref "SW4")
      (value "6x6x5")
      (footprint "KS TSW-SMD-6*6*4.3")
      (description "贴片6x6轻触开关")
      (fields (field (name "版权归属") "源创客"))
      (libsource (lib "ZZF_Library") (part "KS  TSW SMD-6x6"))
    )
    (comp (ref "SW5")
      (value "6x6x5")
      (footprint "KS TSW-SMD-6*6*4.3")
      (description "贴片6x6轻触开关")
      (fields (field (name "版权归属") "源创客"))
      (libsource (lib "ZZF_Library") (part "KS  TSW SMD-6x6"))
    )
    (comp (ref "SW6")
      (value "6x6x5")
      (footprint "KS TSW-SMD-6*6*4.3")
      (description "贴片6x6轻触开关")
      (fields (field (name "版权归属") "源创客"))
      (libsource (lib "ZZF_Library") (part "KS  TSW SMD-6x6"))
    )
    (comp (ref "U3")
      (value "SP3232E")
      (footprint "TSSOP16")
      (description "RS232")
      (libsource (lib "ZZF_Library") (part "SP3232E"))
    )
    (comp (ref "U4")
      (value "MP3221")
      (footprint "SOT23-6L")
      (description "DC-DC芯片")
      (libsource (lib "ZZF_Library") (part "MP3221"))
    )
    (comp (ref "U5")
      (value "SP3232E")
      (footprint "TSSOP16")
      (description "RS232")
      (libsource (lib "ZZF_Library") (part "SP3232E"))
    )
    (comp (ref "U6")
      (value "GL850G")
      (footprint "SSOP28_N")
      (description "USB芯片")
      (fields
        (field (name "MANUFACTURER_PART_NUMBER") "GL850G-HHG22-M9")
        (field (name "COPYRIGHT") "Copyright (C) 2016 Accelerated Designs. All rights reserved")
      )
      (libsource (lib "ZZF_Library") (part "GL850G"))
    )
    (comp (ref "U7")
      (value "MP2143DJ")
      (footprint "TSOT23-8")
      (description "DC-DC芯片")
      (libsource (lib "ZZF_Library") (part "MP2143DJ"))
    )
    (comp (ref "U8")
      (value "ALC5621")
      (footprint "QFN32_L")
      (description "音频处理芯片")
      (libsource (lib "ZZF_Library") (part "ALC5621"))
    )
    (comp (ref "U9")
      (value "SY6280AAC")
      (footprint "SOT23-5M")
      (description "功率开关芯片")
      (libsource (lib "ZZF_Library") (part "SY6280AAC"))
    )
    (comp (ref "VD3")
      (value "SS34")
      (footprint "D SMC")
      (description "肖特基二极管")
      (fields (field (name "版权归属") "源创客"))
      (libsource (lib "ZZF_Library") (part "SS34"))
    )
    (comp (ref "X1")
      (value "XTAL-12.0M")
      (footprint "XTAL-3225")
      (description "12M晶振")
      (libsource (lib "ZZF_Library") (part "XTAL-12.0M"))
    )
  )
  (nets
    (net (code "1") (name "/CAP-INT") (class "Default")
      (node (ref "P2") (pin "40") (pinfunction "40_40") (pintype "passive"))
      (node (ref "R47") (pin "2") (pinfunction "2_2") (pintype "passive"))
      (node (ref "R48") (pin "2") (pinfunction "2_2") (pintype "passive"))
    )
    (net (code "2") (name "/CAP-WAKE") (class "Default")
      (node (ref "P2") (pin "39") (pinfunction "39_39") (pintype "passive"))
      (node (ref "R46") (pin "2") (pinfunction "2_2") (pintype "passive"))
    )
    (net (code "3") (name "/DE") (class "Default")
      (node (ref "C25") (pin "2") (pinfunction "2_2") (pintype "passive"))
      (node (ref "P2") (pin "34") (pinfunction "34_34") (pintype "passive"))
      (node (ref "R41") (pin "2") (pinfunction "2_2") (pintype "passive"))
    )
    (net (code "4") (name "/GPIOA28") (class "Default")
      (node (ref "R65") (pin "2") (pinfunction "2_2") (pintype "passive"))
    )
    (net (code "5") (name "/GPIOB9") (class "Default")
      (node (ref "R71") (pin "2") (pinfunction "2_2") (pintype "passive"))
    )
    (net (code "6") (name "/GPIOC29") (class "Default")
      (node (ref "R47") (pin "1") (pinfunction "1_1") (pintype "passive"))
    )
    (net (code "7") (name "/HP-L") (class "Default")
      (node (ref "C35") (pin "2") (pinfunction "2_2") (pintype "passive"))
      (node (ref "U8") (pin "30") (pinfunction "LOUT1_30") (pintype "passive"))
    )
    (net (code "8") (name "/HP-R") (class "Default")
      (node (ref "C42") (pin "2") (pinfunction "2_2") (pintype "passive"))
      (node (ref "U8") (pin "29") (pinfunction "ROUT1_29") (pintype "passive"))
    )
    (net (code "9") (name "/HUB-DM1") (class "Default")
      (node (ref "R80") (pin "2") (pinfunction "2_2") (pintype "passive"))
      (node (ref "U6") (pin "27") (pinfunction "DM1_27") (pintype "bidirectional"))
    )
    (net (code "10") (name "/HUB-DM2") (class "Default")
      (node (ref "P11") (pin "18") (pinfunction "18_18") (pintype "passive"))
      (node (ref "U6") (pin "2") (pinfunction "DM2_2") (pintype "bidirectional"))
    )
    (net (code "11") (name "/HUB-DM3") (class "Default")
      (node (ref "P4") (pin "2") (pinfunction "D-_2") (pintype "passive"))
      (node (ref "U6") (pin "8") (pinfunction "DM3_8") (pintype "bidirectional"))
    )
    (net (code "12") (name "/HUB-DM4") (class "Default")
      (node (ref "P3") (pin "2") (pinfunction "D-_2") (pintype "passive"))
      (node (ref "U6") (pin "11") (pinfunction "DM4_11") (pintype "bidirectional"))
    )
    (net (code "13") (name "/HUB-DP1") (class "Default")
      (node (ref "R81") (pin "2") (pinfunction "2_2") (pintype "passive"))
      (node (ref "U6") (pin "28") (pinfunction "DP1_28") (pintype "bidirectional"))
    )
    (net (code "14") (name "/HUB-DP2") (class "Default")
      (node (ref "P11") (pin "19") (pinfunction "19_19") (pintype "passive"))
      (node (ref "U6") (pin "3") (pinfunction "DP2_3") (pintype "bidirectional"))
    )
    (net (code "15") (name "/HUB-DP3") (class "Default")
      (node (ref "P4") (pin "3") (pinfunction "D+_3") (pintype "passive"))
      (node (ref "U6") (pin "9") (pinfunction "DP3_9") (pintype "bidirectional"))
    )
    (net (code "16") (name "/HUB-DP4") (class "Default")
      (node (ref "P3") (pin "3") (pinfunction "D+_3") (pintype "passive"))
      (node (ref "U6") (pin "12") (pinfunction "DP4_12") (pintype "bidirectional"))
    )
    (net (code "17") (name "/L-B0") (class "Default")
      (node (ref "P2") (pin "21") (pinfunction "21_21") (pintype "passive"))
      (node (ref "R23") (pin "2") (pinfunction "2_2") (pintype "passive"))
    )
    (net (code "18") (name "/L-B1") (class "Default")
      (node (ref "P2") (pin "22") (pinfunction "22_22") (pintype "passive"))
      (node (ref "R24") (pin "2") (pinfunction "2_2") (pintype "passive"))
    )
    (net (code "19") (name "/L-B2") (class "Default")
      (node (ref "P2") (pin "23") (pinfunction "23_23") (pintype "passive"))
      (node (ref "R25") (pin "2") (pinfunction "2_2") (pintype "passive"))
    )
    (net (code "20") (name "/L-B3") (class "Default")
      (node (ref "P2") (pin "24") (pinfunction "24_24") (pintype "passive"))
      (node (ref "R26") (pin "2") (pinfunction "2_2") (pintype "passive"))
    )
    (net (code "21") (name "/L-B4") (class "Default")
      (node (ref "P2") (pin "25") (pinfunction "25_25") (pintype "passive"))
      (node (ref "R27") (pin "2") (pinfunction "2_2") (pintype "passive"))
    )
    (net (code "22") (name "/L-B5") (class "Default")
      (node (ref "P2") (pin "26") (pinfunction "26_26") (pintype "passive"))
      (node (ref "R28") (pin "2") (pinfunction "2_2") (pintype "passive"))
    )
    (net (code "23") (name "/L-B6") (class "Default")
      (node (ref "P2") (pin "27") (pinfunction "27_27") (pintype "passive"))
      (node (ref "R29") (pin "2") (pinfunction "2_2") (pintype "passive"))
    )
    (net (code "24") (name "/L-B7") (class "Default")
      (node (ref "P2") (pin "28") (pinfunction "28_28") (pintype "passive"))
      (node (ref "R30") (pin "2") (pinfunction "2_2") (pintype "passive"))
    )
    (net (code "25") (name "/L-DCLK") (class "Default")
      (node (ref "C21") (pin "2") (pinfunction "2_2") (pintype "passive"))
      (node (ref "P2") (pin "30") (pinfunction "30_30") (pintype "passive"))
      (node (ref "R31") (pin "2") (pinfunction "2_2") (pintype "passive"))
    )
    (net (code "26") (name "/L-G0") (class "Default")
      (node (ref "P2") (pin "13") (pinfunction "13_13") (pintype "passive"))
      (node (ref "R12") (pin "2") (pinfunction "2_2") (pintype "passive"))
    )
    (net (code "27") (name "/L-G1") (class "Default")
      (node (ref "P2") (pin "14") (pinfunction "14_14") (pintype "passive"))
      (node (ref "R13") (pin "2") (pinfunction "2_2") (pintype "passive"))
    )
    (net (code "28") (name "/L-G2") (class "Default")
      (node (ref "P2") (pin "15") (pinfunction "15_15") (pintype "passive"))
      (node (ref "R14") (pin "2") (pinfunction "2_2") (pintype "passive"))
    )
    (net (code "29") (name "/L-G3") (class "Default")
      (node (ref "P2") (pin "16") (pinfunction "16_16") (pintype "passive"))
      (node (ref "R16") (pin "2") (pinfunction "2_2") (pintype "passive"))
    )
    (net (code "30") (name "/L-G4") (class "Default")
      (node (ref "P2") (pin "17") (pinfunction "17_17") (pintype "passive"))
      (node (ref "R18") (pin "2") (pinfunction "2_2") (pintype "passive"))
    )
    (net (code "31") (name "/L-G5") (class "Default")
      (node (ref "P2") (pin "18") (pinfunction "18_18") (pintype "passive"))
      (node (ref "R19") (pin "2") (pinfunction "2_2") (pintype "passive"))
    )
    (net (code "32") (name "/L-G6") (class "Default")
      (node (ref "P2") (pin "19") (pinfunction "19_19") (pintype "passive"))
      (node (ref "R21") (pin "2") (pinfunction "2_2") (pintype "passive"))
    )
    (net (code "33") (name "/L-G7") (class "Default")
      (node (ref "P2") (pin "20") (pinfunction "20_20") (pintype "passive"))
      (node (ref "R22") (pin "2") (pinfunction "2_2") (pintype "passive"))
    )
    (net (code "34") (name "/L-R0") (class "Default")
      (node (ref "P2") (pin "5") (pinfunction "5_5") (pintype "passive"))
      (node (ref "R1") (pin "2") (pinfunction "2_2") (pintype "passive"))
    )
    (net (code "35") (name "/L-R1") (class "Default")
      (node (ref "P2") (pin "6") (pinfunction "6_6") (pintype "passive"))
      (node (ref "R2") (pin "2") (pinfunction "2_2") (pintype "passive"))
    )
    (net (code "36") (name "/L-R2") (class "Default")
      (node (ref "P2") (pin "7") (pinfunction "7_7") (pintype "passive"))
      (node (ref "R3") (pin "2") (pinfunction "2_2") (pintype "passive"))
    )
    (net (code "37") (name "/L-R3") (class "Default")
      (node (ref "P2") (pin "8") (pinfunction "8_8") (pintype "passive"))
      (node (ref "R4") (pin "2") (pinfunction "2_2") (pintype "passive"))
    )
    (net (code "38") (name "/L-R4") (class "Default")
      (node (ref "P2") (pin "9") (pinfunction "9_9") (pintype "passive"))
      (node (ref "R5") (pin "2") (pinfunction "2_2") (pintype "passive"))
    )
    (net (code "39") (name "/L-R5") (class "Default")
      (node (ref "P2") (pin "10") (pinfunction "10_10") (pintype "passive"))
      (node (ref "R8") (pin "2") (pinfunction "2_2") (pintype "passive"))
    )
    (net (code "40") (name "/L-R6") (class "Default")
      (node (ref "P2") (pin "11") (pinfunction "11_11") (pintype "passive"))
      (node (ref "R9") (pin "2") (pinfunction "2_2") (pintype "passive"))
    )
    (net (code "41") (name "/L-R7") (class "Default")
      (node (ref "P2") (pin "12") (pinfunction "12_12") (pintype "passive"))
      (node (ref "R11") (pin "2") (pinfunction "2_2") (pintype "passive"))
    )
    (net (code "42") (name "/LCD-B0") (class "Default")
      (node (ref "R23") (pin "1") (pinfunction "1_1") (pintype "passive"))
    )
    (net (code "43") (name "/LCD-B1") (class "Default")
      (node (ref "R24") (pin "1") (pinfunction "1_1") (pintype "passive"))
    )
    (net (code "44") (name "/LCD-B2") (class "Default")
      (node (ref "R25") (pin "1") (pinfunction "1_1") (pintype "passive"))
    )
    (net (code "45") (name "/LCD-B3") (class "Default")
      (node (ref "R26") (pin "1") (pinfunction "1_1") (pintype "passive"))
    )
    (net (code "46") (name "/LCD-B4") (class "Default")
      (node (ref "R27") (pin "1") (pinfunction "1_1") (pintype "passive"))
    )
    (net (code "47") (name "/LCD-B5") (class "Default")
      (node (ref "R28") (pin "1") (pinfunction "1_1") (pintype "passive"))
    )
    (net (code "48") (name "/LCD-B6") (class "Default")
      (node (ref "R29") (pin "1") (pinfunction "1_1") (pintype "passive"))
    )
    (net (code "49") (name "/LCD-B7") (class "Default")
      (node (ref "R30") (pin "1") (pinfunction "1_1") (pintype "passive"))
    )
    (net (code "50") (name "/LCD-CLK") (class "Default")
      (node (ref "C20") (pin "2") (pinfunction "2_2") (pintype "passive"))
      (node (ref "R31") (pin "1") (pinfunction "1_1") (pintype "passive"))
    )
    (net (code "51") (name "/LCD-DE") (class "Default")
      (node (ref "C24") (pin "2") (pinfunction "2_2") (pintype "passive"))
      (node (ref "R41") (pin "1") (pinfunction "1_1") (pintype "passive"))
    )
    (net (code "52") (name "/LCD-EN") (class "Default")
      (node (ref "P2") (pin "31") (pinfunction "31_31") (pintype "passive"))
      (node (ref "R35") (pin "2") (pinfunction "2_2") (pintype "passive"))
    )
    (net (code "53") (name "/LCD-G0") (class "Default")
      (node (ref "R12") (pin "1") (pinfunction "1_1") (pintype "passive"))
    )
    (net (code "54") (name "/LCD-G1") (class "Default")
      (node (ref "R13") (pin "1") (pinfunction "1_1") (pintype "passive"))
    )
    (net (code "55") (name "/LCD-G2") (class "Default")
      (node (ref "R14") (pin "1") (pinfunction "1_1") (pintype "passive"))
    )
    (net (code "56") (name "/LCD-G3") (class "Default")
      (node (ref "R16") (pin "1") (pinfunction "1_1") (pintype "passive"))
    )
    (net (code "57") (name "/LCD-G4") (class "Default")
      (node (ref "R18") (pin "1") (pinfunction "1_1") (pintype "passive"))
    )
    (net (code "58") (name "/LCD-G5") (class "Default")
      (node (ref "R19") (pin "1") (pinfunction "1_1") (pintype "passive"))
    )
    (net (code "59") (name "/LCD-G6") (class "Default")
      (node (ref "R21") (pin "1") (pinfunction "1_1") (pintype "passive"))
    )
    (net (code "60") (name "/LCD-G7") (class "Default")
      (node (ref "R22") (pin "1") (pinfunction "1_1") (pintype "passive"))
    )
    (net (code "61") (name "/LCD-H") (class "Default")
      (node (ref "R38") (pin "1") (pinfunction "1_1") (pintype "passive"))
    )
    (net (code "62") (name "/LCD-HH") (class "Default")
      (node (ref "P2") (pin "32") (pinfunction "32_32") (pintype "passive"))
      (node (ref "R38") (pin "2") (pinfunction "2_2") (pintype "passive"))
    )
    (net (code "63") (name "/LCD-PWM") (class "Default")
      (node (ref "P2") (pin "1") (pinfunction "1_1") (pintype "passive"))
    )
    (net (code "64") (name "/LCD-R0") (class "Default")
      (node (ref "R1") (pin "1") (pinfunction "1_1") (pintype "passive"))
    )
    (net (code "65") (name "/LCD-R1") (class "Default")
      (node (ref "R2") (pin "1") (pinfunction "1_1") (pintype "passive"))
    )
    (net (code "66") (name "/LCD-R2") (class "Default")
      (node (ref "R3") (pin "1") (pinfunction "1_1") (pintype "passive"))
    )
    (net (code "67") (name "/LCD-R3") (class "Default")
      (node (ref "R4") (pin "1") (pinfunction "1_1") (pintype "passive"))
    )
    (net (code "68") (name "/LCD-R4") (class "Default")
      (node (ref "R5") (pin "1") (pinfunction "1_1") (pintype "passive"))
    )
    (net (code "69") (name "/LCD-R5") (class "Default")
      (node (ref "R8") (pin "1") (pinfunction "1_1") (pintype "passive"))
    )
    (net (code "70") (name "/LCD-R6") (class "Default")
      (node (ref "R9") (pin "1") (pinfunction "1_1") (pintype "passive"))
    )
    (net (code "71") (name "/LCD-R7") (class "Default")
      (node (ref "R11") (pin "1") (pinfunction "1_1") (pintype "passive"))
    )
    (net (code "72") (name "/LCD-V") (class "Default")
      (node (ref "R40") (pin "1") (pinfunction "1_1") (pintype "passive"))
    )
    (net (code "73") (name "/LCD-VV") (class "Default")
      (node (ref "P2") (pin "33") (pinfunction "33_33") (pintype "passive"))
      (node (ref "R40") (pin "2") (pinfunction "2_2") (pintype "passive"))
    )
    (net (code "74") (name "/LED1") (class "Default")
      (node (ref "R91") (pin "2") (pinfunction "2_2") (pintype "passive"))
    )
    (net (code "75") (name "/LED2") (class "Default")
      (node (ref "R87") (pin "2") (pinfunction "2_2") (pintype "passive"))
    )
    (net (code "76") (name "/LINK-LED") (class "Default")
      (node (ref "P11") (pin "2") (pinfunction "2_2") (pintype "passive"))
    )
    (net (code "77") (name "/MCU-HP-DET") (class "Default")
      (node (ref "R49") (pin "2") (pinfunction "2_2") (pintype "passive"))
    )
    (net (code "78") (name "/MCU-I2S-BCK") (class "Default")
      (node (ref "U8") (pin "8") (pinfunction "BCLK_8") (pintype "passive"))
    )
    (net (code "79") (name "/MCU-I2S-LRCK") (class "Default")
      (node (ref "U8") (pin "7") (pinfunction "LRC_7") (pintype "passive"))
    )
    (net (code "80") (name "/MCU-I2S-MCLK") (class "Default")
      (node (ref "U8") (pin "11") (pinfunction "MCLK_11") (pintype "passive"))
    )
    (net (code "81") (name "/MCU-I2S-SDIN") (class "Default")
      (node (ref "U8") (pin "9") (pinfunction "ADCDAT_9") (pintype "passive"))
    )
    (net (code "82") (name "/MCU-I2S-SDOUT") (class "Default")
      (node (ref "U8") (pin "10") (pinfunction "DACDAT_10") (pintype "passive"))
    )
    (net (code "83") (name "/MCU-KEY-VOLDN") (class "Default")
      (node (ref "R67") (pin "2") (pinfunction "2_2") (pintype "passive"))
    )
    (net (code "84") (name "/MCU-KEY-VOLUP") (class "Default")
      (node (ref "R69") (pin "2") (pinfunction "2_2") (pintype "passive"))
    )
    (net (code "85") (name "/MCU-NRESETIN") (class "Default")
      (node (ref "R82") (pin "1") (pinfunction "1_1") (pintype "passive"))
    )
    (net (code "86") (name "/MCU-OTG-PERON") (class "Default")
      (node (ref "R83") (pin "1") (pinfunction "1_1") (pintype "passive"))
    )
    (net (code "87") (name "/MCU-OTG-USB+") (class "Default")
      (node (ref "P20") (pin "3") (pinfunction "D+_3") (pintype "passive"))
    )
    (net (code "88") (name "/MCU-OTG-USB-") (class "Default")
      (node (ref "P20") (pin "2") (pinfunction "D-_2") (pintype "passive"))
    )
    (net (code "89") (name "/MCU-PWRKEY") (class "Default")
      (node (ref "C62") (pin "1") (pinfunction "1_1") (pintype "passive"))
      (node (ref "R85") (pin "1") (pinfunction "1_1") (pintype "passive"))
    )
    (net (code "90") (name "/MCU-RESETOUT") (class "Default")
      (node (ref "R46") (pin "1") (pinfunction "1_1") (pintype "passive"))
    )
    (net (code "91") (name "/MCU-SCL-1") (class "Default")
      (node (ref "R43") (pin "1") (pinfunction "1_1") (pintype "passive"))
    )
    (net (code "92") (name "/MCU-SCL0") (class "Default")
      (node (ref "R88") (pin "1") (pinfunction "1_1") (pintype "passive"))
    )
    (net (code "93") (name "/MCU-SD0-CD") (class "Default")
      (node (ref "P12") (pin "9") (pinfunction "DET_9") (pintype "passive"))
    )
    (net (code "94") (name "/MCU-SD0-CLK") (class "Default")
      (node (ref "R62") (pin "1") (pinfunction "1_1") (pintype "passive"))
    )
    (net (code "95") (name "/MCU-SD0-CMD") (class "Default")
      (node (ref "P12") (pin "3") (pinfunction "CMD_3") (pintype "passive"))
      (node (ref "R53") (pin "1") (pinfunction "1_1") (pintype "passive"))
    )
    (net (code "96") (name "/MCU-SD0-D0") (class "Default")
      (node (ref "P12") (pin "7") (pinfunction "DAT0_7") (pintype "passive"))
      (node (ref "R51") (pin "1") (pinfunction "1_1") (pintype "passive"))
    )
    (net (code "97") (name "/MCU-SD0-D1") (class "Default")
      (node (ref "P12") (pin "8") (pinfunction "DAT1_8") (pintype "passive"))
      (node (ref "R52") (pin "1") (pinfunction "1_1") (pintype "passive"))
    )
    (net (code "98") (name "/MCU-SD0-D2") (class "Default")
      (node (ref "P12") (pin "1") (pinfunction "DAT2_1") (pintype "passive"))
      (node (ref "R55") (pin "1") (pinfunction "1_1") (pintype "passive"))
    )
    (net (code "99") (name "/MCU-SD0-D3") (class "Default")
      (node (ref "P12") (pin "2") (pinfunction "DAT3_2") (pintype "passive"))
      (node (ref "R54") (pin "1") (pinfunction "1_1") (pintype "passive"))
    )
    (net (code "100") (name "/MCU-SDA-1") (class "Default")
      (node (ref "R45") (pin "1") (pinfunction "1_1") (pintype "passive"))
    )
    (net (code "101") (name "/MCU-SDA0") (class "Default")
      (node (ref "R90") (pin "1") (pinfunction "1_1") (pintype "passive"))
    )
    (net (code "102") (name "/MCU-USB-HOST-D+") (class "Default")
      (node (ref "U6") (pin "26") (pinfunction "DP0_26") (pintype "bidirectional"))
    )
    (net (code "103") (name "/MCU-USB-HOST-D-") (class "Default")
      (node (ref "U6") (pin "25") (pinfunction "DM0_25") (pintype "bidirectional"))
    )
    (net (code "104") (name "/MCU-USB-ID") (class "Default")
      (node (ref "P20") (pin "4") (pinfunction "ID_4") (pintype "passive"))
    )
    (net (code "105") (name "/MCU-VG-EN") (class "Default")
      (node (ref "R35") (pin "1") (pinfunction "1_1") (pintype "passive"))
    )
    (net (code "106") (name "/MDI0-N") (class "Default")
      (node (ref "P11") (pin "5") (pinfunction "5_5") (pintype "passive"))
    )
    (net (code "107") (name "/MDI0-P") (class "Default")
      (node (ref "P11") (pin "4") (pinfunction "4_4") (pintype "passive"))
    )
    (net (code "108") (name "/MDI1-N") (class "Default")
      (node (ref "P11") (pin "7") (pinfunction "7_7") (pintype "passive"))
    )
    (net (code "109") (name "/MDI1-P") (class "Default")
      (node (ref "P11") (pin "6") (pinfunction "6_6") (pintype "passive"))
    )
    (net (code "110") (name "/MDI2-N") (class "Default")
      (node (ref "P11") (pin "9") (pinfunction "9_9") (pintype "passive"))
    )
    (net (code "111") (name "/MDI2-P") (class "Default")
      (node (ref "P11") (pin "8") (pinfunction "8_8") (pintype "passive"))
    )
    (net (code "112") (name "/MDI3-N") (class "Default")
      (node (ref "P11") (pin "11") (pinfunction "11_11") (pintype "passive"))
    )
    (net (code "113") (name "/MDI3-P") (class "Default")
      (node (ref "P11") (pin "10") (pinfunction "10_10") (pintype "passive"))
    )
    (net (code "114") (name "/MIC-BIAS") (class "Default")
      (node (ref "R60") (pin "1") (pinfunction "1_1") (pintype "passive"))
      (node (ref "U8") (pin "32") (pinfunction "MICBIAS_32") (pintype "passive"))
    )
    (net (code "115") (name "/MICN") (class "Default")
      (node (ref "C57") (pin "1") (pinfunction "1_1") (pintype "passive"))
      (node (ref "M1") (pin "2") (pinfunction "2_2") (pintype "passive"))
      (node (ref "R63") (pin "2") (pinfunction "2_2") (pintype "passive"))
    )
    (net (code "116") (name "/MICP") (class "Default")
      (node (ref "C45") (pin "1") (pinfunction "1_1") (pintype "passive"))
      (node (ref "C55") (pin "1") (pinfunction "1_1") (pintype "passive"))
      (node (ref "M1") (pin "1") (pinfunction "1_1") (pintype "passive"))
      (node (ref "R61") (pin "2") (pinfunction "2_2") (pintype "passive"))
    )
    (net (code "117") (name "/PC-RXD0") (class "Default")
      (node (ref "P6") (pin "2") (pinfunction "2_2") (pintype "passive"))
      (node (ref "U3") (pin "8") (pinfunction "R2IN_8") (pintype "input"))
    )
    (net (code "118") (name "/PC-RXD1") (class "Default")
      (node (ref "P7") (pin "2") (pinfunction "2_2") (pintype "passive"))
      (node (ref "U3") (pin "13") (pinfunction "R1IN_13") (pintype "input"))
    )
    (net (code "119") (name "/PC-RXD2") (class "Default")
      (node (ref "P8") (pin "2") (pinfunction "2_2") (pintype "passive"))
      (node (ref "U5") (pin "8") (pinfunction "R2IN_8") (pintype "input"))
    )
    (net (code "120") (name "/PC-RXD3") (class "Default")
      (node (ref "P9") (pin "2") (pinfunction "2_2") (pintype "passive"))
      (node (ref "U5") (pin "13") (pinfunction "R1IN_13") (pintype "input"))
    )
    (net (code "121") (name "/PC-TXD0") (class "Default")
      (node (ref "P6") (pin "3") (pinfunction "3_3") (pintype "passive"))
      (node (ref "U3") (pin "14") (pinfunction "T1OUT_14") (pintype "output"))
    )
    (net (code "122") (name "/PC-TXD1") (class "Default")
      (node (ref "P7") (pin "3") (pinfunction "3_3") (pintype "passive"))
      (node (ref "U3") (pin "7") (pinfunction "T2OUT_7") (pintype "output"))
    )
    (net (code "123") (name "/PC-TXD2") (class "Default")
      (node (ref "P8") (pin "3") (pinfunction "3_3") (pintype "passive"))
      (node (ref "U5") (pin "14") (pinfunction "T1OUT_14") (pintype "output"))
    )
    (net (code "124") (name "/PC-TXD3") (class "Default")
      (node (ref "P9") (pin "3") (pinfunction "3_3") (pintype "passive"))
      (node (ref "U5") (pin "7") (pinfunction "T2OUT_7") (pintype "output"))
    )
    (net (code "125") (name "/SIM-CLK") (class "Default")
      (node (ref "P13") (pin "3") (pinfunction "CLK_3") (pintype "passive"))
      (node (ref "R68") (pin "2") (pinfunction "2_2") (pintype "passive"))
    )
    (net (code "126") (name "/SIM-DATA") (class "Default")
      (node (ref "P13") (pin "7") (pinfunction "ID_7") (pintype "passive"))
      (node (ref "R64") (pin "2") (pinfunction "2_2") (pintype "passive"))
      (node (ref "R66") (pin "2") (pinfunction "2_2") (pintype "passive"))
    )
    (net (code "127") (name "/SIM-RST") (class "Default")
      (node (ref "C53") (pin "2") (pinfunction "2_2") (pintype "passive"))
      (node (ref "P13") (pin "2") (pinfunction "RST_2") (pintype "passive"))
      (node (ref "R70") (pin "2") (pinfunction "2_2") (pintype "passive"))
    )
    (net (code "128") (name "/SIM-VDD") (class "Default")
      (node (ref "C52") (pin "2") (pinfunction "2_2") (pintype "passive"))
      (node (ref "P13") (pin "1") (pinfunction "VCC_1") (pintype "passive"))
      (node (ref "P13") (pin "6") (pinfunction "NC_6") (pintype "passive"))
      (node (ref "P14") (pin "8") (pinfunction "VREG_UIM_8") (pintype "passive"))
      (node (ref "R64") (pin "1") (pinfunction "1_1") (pintype "passive"))
    )
    (net (code "129") (name "/SPEED-LED") (class "Default")
      (node (ref "P11") (pin "3") (pinfunction "3_3") (pintype "passive"))
    )
    (net (code "130") (name "/TP-SCL") (class "Default")
      (node (ref "P2") (pin "37") (pinfunction "37_37") (pintype "passive"))
      (node (ref "R43") (pin "2") (pinfunction "2_2") (pintype "passive"))
    )
    (net (code "131") (name "/TP-SDA") (class "Default")
      (node (ref "P2") (pin "38") (pinfunction "38_38") (pintype "passive"))
      (node (ref "R45") (pin "2") (pinfunction "2_2") (pintype "passive"))
    )
    (net (code "132") (name "/UARTRXD0") (class "Default")
      (node (ref "U3") (pin "9") (pinfunction "R2OUT_9") (pintype "output"))
    )
    (net (code "133") (name "/UARTRXD1") (class "Default")
      (node (ref "U3") (pin "12") (pinfunction "R1OUT_12") (pintype "output"))
    )
    (net (code "134") (name "/UARTRXD2") (class "Default")
      (node (ref "U5") (pin "9") (pinfunction "R2OUT_9") (pintype "output"))
    )
    (net (code "135") (name "/UARTRXD3") (class "Default")
      (node (ref "U5") (pin "12") (pinfunction "R1OUT_12") (pintype "output"))
    )
    (net (code "136") (name "/UARTTXD0") (class "Default")
      (node (ref "U3") (pin "10") (pinfunction "T2IN_10") (pintype "input"))
    )
    (net (code "137") (name "/UARTTXD1") (class "Default")
      (node (ref "U3") (pin "11") (pinfunction "T1IN_11") (pintype "input"))
    )
    (net (code "138") (name "/UARTTXD2") (class "Default")
      (node (ref "U5") (pin "10") (pinfunction "T2IN_10") (pintype "input"))
    )
    (net (code "139") (name "/UARTTXD3") (class "Default")
      (node (ref "U5") (pin "11") (pinfunction "T1IN_11") (pintype "input"))
    )
    (net (code "140") (name "/UARTTXD4") (class "Default")
      (node (ref "R48") (pin "1") (pinfunction "1_1") (pintype "passive"))
    )
    (net (code "141") (name "/V33-HUB") (class "Default")
      (node (ref "C27") (pin "1") (pinfunction "1_1") (pintype "passive"))
      (node (ref "C29") (pin "1") (pinfunction "1_1") (pintype "passive"))
      (node (ref "R37") (pin "1") (pinfunction "1_1") (pintype "passive"))
      (node (ref "U6") (pin "1") (pinfunction "AVDD_1") (pintype "power_in"))
      (node (ref "U6") (pin "10") (pinfunction "AVDD_10") (pintype "power_in"))
      (node (ref "U6") (pin "16") (pinfunction "DVDD_16") (pintype "power_in"))
      (node (ref "U6") (pin "24") (pinfunction "V33_24") (pintype "power_in"))
      (node (ref "U6") (pin "5") (pinfunction "AVDD_5") (pintype "power_in"))
    )
    (net (code "142") (name "/XTAL1") (class "Default")
      (node (ref "C26") (pin "2") (pinfunction "2_2") (pintype "passive"))
      (node (ref "R44") (pin "2") (pinfunction "2_2") (pintype "passive"))
      (node (ref "U6") (pin "6") (pinfunction "X1_6") (pintype "input"))
      (node (ref "X1") (pin "3") (pinfunction "OSC2_3") (pintype "passive"))
    )
    (net (code "143") (name "/XTAL2") (class "Default")
      (node (ref "C31") (pin "2") (pinfunction "2_2") (pintype "passive"))
      (node (ref "R44") (pin "1") (pinfunction "1_1") (pintype "passive"))
      (node (ref "U6") (pin "7") (pinfunction "X2_7") (pintype "output"))
      (node (ref "X1") (pin "1") (pinfunction "OSC1_1") (pintype "passive"))
    )
    (net (code "144") (name "DC5V-OTG") (class "Default")
      (node (ref "C58") (pin "1") (pinfunction "1_1") (pintype "passive"))
      (node (ref "C59") (pin "2") (pinfunction "2_2") (pintype "passive"))
      (node (ref "P20") (pin "1") (pinfunction "VBUS_1") (pintype "passive"))
      (node (ref "U9") (pin "1") (pinfunction "OUT_1") (pintype "passive"))
    )
    (net (code "145") (name "GND") (class "Default")
      (node (ref "C12") (pin "1") (pinfunction "1_1") (pintype "passive"))
      (node (ref "C13") (pin "1") (pinfunction "1_1") (pintype "passive"))
      (node (ref "C14") (pin "1") (pinfunction "1_1") (pintype "passive"))
      (node (ref "C18") (pin "2") (pinfunction "2_2") (pintype "passive"))
      (node (ref "C20") (pin "1") (pinfunction "1_1") (pintype "passive"))
      (node (ref "C21") (pin "1") (pinfunction "1_1") (pintype "passive"))
      (node (ref "C23") (pin "1") (pinfunction "1_1") (pintype "passive"))
      (node (ref "C24") (pin "1") (pinfunction "1_1") (pintype "passive"))
      (node (ref "C25") (pin "1") (pinfunction "1_1") (pintype "passive"))
      (node (ref "C26") (pin "1") (pinfunction "1_1") (pintype "passive"))
      (node (ref "C27") (pin "2") (pinfunction "2_2") (pintype "passive"))
      (node (ref "C28") (pin "1") (pinfunction "1_1") (pintype "passive"))
      (node (ref "C29") (pin "2") (pinfunction "2_2") (pintype "passive"))
      (node (ref "C30") (pin "1") (pinfunction "1_1") (pintype "passive"))
      (node (ref "C31") (pin "1") (pinfunction "1_1") (pintype "passive"))
      (node (ref "C32") (pin "1") (pinfunction "1_1") (pintype "passive"))
      (node (ref "C33") (pin "1") (pinfunction "1_1") (pintype "passive"))
      (node (ref "C34") (pin "1") (pinfunction "1_1") (pintype "passive"))
      (node (ref "C36") (pin "1") (pinfunction "1_1") (pintype "passive"))
      (node (ref "C37") (pin "1") (pinfunction "1_1") (pintype "passive"))
      (node (ref "C38") (pin "1") (pinfunction "1_1") (pintype "passive"))
      (node (ref "C39") (pin "1") (pinfunction "1_1") (pintype "passive"))
      (node (ref "C40") (pin "1") (pinfunction "1_1") (pintype "passive"))
      (node (ref "C41") (pin "1") (pinfunction "1_1") (pintype "passive"))
      (node (ref "C43") (pin "1") (pinfunction "1_1") (pintype "passive"))
      (node (ref "C44") (pin "1") (pinfunction "1_1") (pintype "passive"))
      (node (ref "C45") (pin "2") (pinfunction "2_2") (pintype "passive"))
      (node (ref "C46") (pin "1") (pinfunction "1_1") (pintype "passive"))
      (node (ref "C47") (pin "1") (pinfunction "1_1") (pintype "passive"))
      (node (ref "C48") (pin "1") (pinfunction "1_1") (pintype "passive"))
      (node (ref "C49") (pin "1") (pinfunction "1_1") (pintype "passive"))
      (node (ref "C50") (pin "2") (pinfunction "2_2") (pintype "passive"))
      (node (ref "C51") (pin "1") (pinfunction "1_1") (pintype "passive"))
      (node (ref "C52") (pin "1") (pinfunction "1_1") (pintype "passive"))
      (node (ref "C53") (pin "1") (pinfunction "1_1") (pintype "passive"))
      (node (ref "C54") (pin "2") (pinfunction "2_2") (pintype "passive"))
      (node (ref "C56") (pin "2") (pinfunction "2_2") (pintype "passive"))
      (node (ref "C58") (pin "2") (pinfunction "2_2") (pintype "passive"))
      (node (ref "C59") (pin "1") (pinfunction "1_1") (pintype "passive"))
      (node (ref "C60") (pin "2") (pinfunction "2_2") (pintype "passive"))
      (node (ref "C61") (pin "2") (pinfunction "2_2") (pintype "passive"))
      (node (ref "C62") (pin "2") (pinfunction "2_2") (pintype "passive"))
      (node (ref "C9") (pin "2") (pinfunction "2_2") (pintype "passive"))
      (node (ref "P10") (pin "1") (pintype "passive"))
      (node (ref "P11") (pin "0") (pinfunction "0_0") (pintype "passive"))
      (node (ref "P11") (pin "1") (pinfunction "1_1") (pintype "passive"))
      (node (ref "P11") (pin "12") (pinfunction "12_12") (pintype "passive"))
      (node (ref "P11") (pin "20") (pinfunction "20_20") (pintype "passive"))
      (node (ref "P12") (pin "10") (pinfunction "10_10") (pintype "passive"))
      (node (ref "P12") (pin "11") (pinfunction "11_11") (pintype "passive"))
      (node (ref "P12") (pin "12") (pinfunction "12_12") (pintype "passive"))
      (node (ref "P12") (pin "13") (pinfunction "13_13") (pintype "passive"))
      (node (ref "P12") (pin "6") (pinfunction "VSS_6") (pintype "passive"))
      (node (ref "P13") (pin "5") (pinfunction "GND_5") (pintype "passive"))
      (node (ref "P13") (pin "9") (pinfunction "GND_9") (pintype "passive"))
      (node (ref "P14") (pin "15") (pinfunction "GND3_15") (pintype "passive"))
      (node (ref "P14") (pin "18") (pinfunction "GND4_18") (pintype "passive"))
      (node (ref "P14") (pin "21") (pinfunction "GND5_21") (pintype "passive"))
      (node (ref "P14") (pin "26") (pinfunction "GND6_26") (pintype "passive"))
      (node (ref "P14") (pin "27") (pinfunction "GND7_27") (pintype "passive"))
      (node (ref "P14") (pin "29") (pinfunction "GND8_29") (pintype "passive"))
      (node (ref "P14") (pin "35") (pinfunction "GND10_35") (pintype "passive"))
      (node (ref "P14") (pin "37") (pinfunction "GND11_37") (pintype "passive"))
      (node (ref "P14") (pin "4") (pinfunction "GND1_4") (pintype "passive"))
      (node (ref "P14") (pin "40") (pinfunction "GND12_40") (pintype "passive"))
      (node (ref "P14") (pin "43") (pinfunction "GND13_43") (pintype "passive"))
      (node (ref "P14") (pin "50") (pinfunction "GND14_50") (pintype "passive"))
      (node (ref "P14") (pin "53") (pinfunction "S1_53") (pintype "passive"))
      (node (ref "P14") (pin "54") (pinfunction "S2_54") (pintype "passive"))
      (node (ref "P14") (pin "9") (pinfunction "GND2_9") (pintype "passive"))
      (node (ref "P2") (pin "0") (pinfunction "0_0") (pintype "passive"))
      (node (ref "P2") (pin "29") (pinfunction "29_29") (pintype "passive"))
      (node (ref "P2") (pin "3") (pinfunction "3_3") (pintype "passive"))
      (node (ref "P2") (pin "36") (pinfunction "36_36") (pintype "passive"))
      (node (ref "P20") (pin "0") (pinfunction "5_0") (pintype "passive"))
      (node (ref "P20") (pin "5") (pinfunction "GND_5") (pintype "passive"))
      (node (ref "P3") (pin "4") (pinfunction "GND_4") (pintype "passive"))
      (node (ref "P3") (pin "5") (pinfunction "5_5") (pintype "passive"))
      (node (ref "P3") (pin "6") (pinfunction "6_6") (pintype "passive"))
      (node (ref "P4") (pin "4") (pinfunction "GND_4") (pintype "passive"))
      (node (ref "P4") (pin "5") (pinfunction "5_5") (pintype "passive"))
      (node (ref "P4") (pin "6") (pinfunction "6_6") (pintype "passive"))
      (node (ref "P6") (pin "1") (pinfunction "1_1") (pintype "passive"))
      (node (ref "P7") (pin "1") (pinfunction "1_1") (pintype "passive"))
      (node (ref "P8") (pin "1") (pinfunction "1_1") (pintype "passive"))
      (node (ref "P9") (pin "1") (pinfunction "1_1") (pintype "passive"))
      (node (ref "Q2") (pin "1") (pinfunction "E_1") (pintype "passive"))
      (node (ref "R17") (pin "1") (pinfunction "1_1") (pintype "passive"))
      (node (ref "R20") (pin "1") (pinfunction "1_1") (pintype "passive"))
      (node (ref "R32") (pin "1") (pinfunction "1_1") (pintype "passive"))
      (node (ref "R34") (pin "2") (pinfunction "2_2") (pintype "passive"))
      (node (ref "R42") (pin "1") (pinfunction "1_1") (pintype "passive"))
      (node (ref "R58") (pin "1") (pinfunction "1_1") (pintype "passive"))
      (node (ref "R59") (pin "1") (pinfunction "1_1") (pintype "passive"))
      (node (ref "R63") (pin "1") (pinfunction "1_1") (pintype "passive"))
      (node (ref "R84") (pin "1") (pinfunction "1_1") (pintype "passive"))
      (node (ref "R86") (pin "1") (pinfunction "1_1") (pintype "passive"))
      (node (ref "R89") (pin "2") (pinfunction "2_2") (pintype "passive"))
      (node (ref "R94") (pin "2") (pinfunction "2_2") (pintype "passive"))
      (node (ref "SW1") (pin "2") (pinfunction "2_2") (pintype "passive"))
      (node (ref "SW1") (pin "3") (pinfunction "3_3") (pintype "passive"))
      (node (ref "SW2") (pin "2") (pinfunction "2_2") (pintype "passive"))
      (node (ref "SW2") (pin "3") (pinfunction "3_3") (pintype "passive"))
      (node (ref "SW3") (pin "2") (pinfunction "2_2") (pintype "passive"))
      (node (ref "SW3") (pin "3") (pinfunction "3_3") (pintype "passive"))
      (node (ref "SW4") (pin "2") (pinfunction "2_2") (pintype "passive"))
      (node (ref "SW4") (pin "3") (pinfunction "3_3") (pintype "passive"))
      (node (ref "SW5") (pin "2") (pinfunction "2_2") (pintype "passive"))
      (node (ref "SW5") (pin "3") (pinfunction "3_3") (pintype "passive"))
      (node (ref "SW6") (pin "2") (pinfunction "2_2") (pintype "passive"))
      (node (ref "SW6") (pin "3") (pinfunction "3_3") (pintype "passive"))
      (node (ref "U3") (pin "15") (pinfunction "GND_15") (pintype "power_in"))
      (node (ref "U4") (pin "2") (pinfunction "GND_2") (pintype "passive"))
      (node (ref "U5") (pin "15") (pinfunction "GND_15") (pintype "power_in"))
      (node (ref "U6") (pin "15") (pinfunction "GND_15") (pintype "power_in"))
      (node (ref "U7") (pin "4") (pinfunction "G_4") (pintype "passive"))
      (node (ref "U7") (pin "6") (pinfunction "AG_6") (pintype "passive"))
      (node (ref "U8") (pin "12") (pinfunction "DGND_12") (pintype "passive"))
      (node (ref "U8") (pin "24") (pinfunction "SPKGND_24") (pintype "passive"))
      (node (ref "U8") (pin "28") (pinfunction "AGND_28") (pintype "passive"))
      (node (ref "U8") (pin "33") (pinfunction "PAD_33") (pintype "passive"))
      (node (ref "U9") (pin "3") (pinfunction "ISET_3") (pintype "passive"))
      (node (ref "X1") (pin "2") (pinfunction "GND_2") (pintype "passive"))
      (node (ref "X1") (pin "4") (pinfunction "GND_4") (pintype "passive"))
    )
    (net (code "146") (name "LVDS-VDD") (class "Default")
      (node (ref "C12") (pin "2") (pinfunction "2_2") (pintype "passive"))
      (node (ref "C47") (pin "2") (pinfunction "2_2") (pintype "passive"))
      (node (ref "C49") (pin "2") (pinfunction "2_2") (pintype "passive"))
      (node (ref "L1") (pin "1") (pinfunction "1_1") (pintype "passive"))
      (node (ref "P2") (pin "2") (pinfunction "2_2") (pintype "passive"))
      (node (ref "Q1") (pin "3") (pinfunction "D_3") (pintype "passive"))
      (node (ref "R7") (pin "2") (pinfunction "2_2") (pintype "passive"))
      (node (ref "U4") (pin "5") (pinfunction "IN_5") (pintype "passive"))
      (node (ref "U8") (pin "26") (pinfunction "SPKVDD_26") (pintype "passive"))
    )
    (net (code "147") (name "Net-(C35-Pad1)") (class "Default")
      (node (ref "C35") (pin "1") (pinfunction "1_1") (pintype "passive"))
      (node (ref "P10") (pin "6") (pinfunction "6_6") (pintype "passive"))
      (node (ref "R49") (pin "1") (pinfunction "1_1") (pintype "passive"))
    )
    (net (code "148") (name "Net-(C42-Pad1)") (class "Default")
      (node (ref "C42") (pin "1") (pinfunction "1_1") (pintype "passive"))
      (node (ref "P10") (pin "4") (pinfunction "4_4") (pintype "passive"))
      (node (ref "P10") (pin "5") (pinfunction "5_5") (pintype "passive"))
    )
    (net (code "149") (name "Net-(C44-Pad2)") (class "Default")
      (node (ref "C44") (pin "2") (pinfunction "2_2") (pintype "passive"))
      (node (ref "R60") (pin "2") (pinfunction "2_2") (pintype "passive"))
      (node (ref "R61") (pin "1") (pinfunction "1_1") (pintype "passive"))
    )
    (net (code "150") (name "Net-(C56-Pad1)") (class "Default")
      (node (ref "C56") (pin "1") (pinfunction "1_1") (pintype "passive"))
      (node (ref "R82") (pin "2") (pinfunction "2_2") (pintype "passive"))
      (node (ref "SW5") (pin "1") (pinfunction "1_1") (pintype "passive"))
      (node (ref "SW5") (pin "4") (pinfunction "4_4") (pintype "passive"))
    )
    (net (code "151") (name "Net-(LED2-PadK)") (class "Default")
      (node (ref "LED2") (pin "K") (pinfunction "K_K") (pintype "passive"))
      (node (ref "R87") (pin "1") (pinfunction "1_1") (pintype "passive"))
    )
    (net (code "152") (name "Net-(LED3-PadK)") (class "Default")
      (node (ref "LED3") (pin "K") (pinfunction "K_K") (pintype "passive"))
      (node (ref "R91") (pin "1") (pinfunction "1_1") (pintype "passive"))
    )
    (net (code "153") (name "Net-(LED6-PadK)") (class "Default")
      (node (ref "LED6") (pin "K") (pinfunction "K_K") (pintype "passive"))
      (node (ref "R94") (pin "1") (pinfunction "1_1") (pintype "passive"))
    )
    (net (code "154") (name "Net-(P10-Pad3)") (class "Default")
      (node (ref "P10") (pin "3") (pinfunction "3_3") (pintype "passive"))
      (node (ref "R50") (pin "1") (pinfunction "1_1") (pintype "passive"))
    )
    (net (code "155") (name "Net-(P12-CLK)") (class "Default")
      (node (ref "P12") (pin "5") (pinfunction "CLK_5") (pintype "passive"))
      (node (ref "R62") (pin "2") (pinfunction "2_2") (pintype "passive"))
    )
    (net (code "156") (name "Net-(P14-UIM_CLK)") (class "Default")
      (node (ref "P14") (pin "12") (pinfunction "UIM_CLK_12") (pintype "passive"))
      (node (ref "R68") (pin "1") (pinfunction "1_1") (pintype "passive"))
    )
    (net (code "157") (name "Net-(P14-UIM_DATA)") (class "Default")
      (node (ref "P14") (pin "10") (pinfunction "UIM_DATA_10") (pintype "passive"))
      (node (ref "R66") (pin "1") (pinfunction "1_1") (pintype "passive"))
    )
    (net (code "158") (name "Net-(P14-UIM_PST)") (class "Default")
      (node (ref "P14") (pin "14") (pinfunction "UIM_PST_14") (pintype "passive"))
      (node (ref "R70") (pin "1") (pinfunction "1_1") (pintype "passive"))
    )
    (net (code "159") (name "Net-(P14-USB_D+)") (class "Default")
      (node (ref "P14") (pin "38") (pinfunction "USB_D+_38") (pintype "passive"))
      (node (ref "R81") (pin "1") (pinfunction "1_1") (pintype "passive"))
    )
    (net (code "160") (name "Net-(P14-USB_D-)") (class "Default")
      (node (ref "P14") (pin "36") (pinfunction "USB_D-_36") (pintype "passive"))
      (node (ref "R80") (pin "1") (pinfunction "1_1") (pintype "passive"))
    )
    (net (code "161") (name "Net-(P14-{slash}LED_WWAN)") (class "Default")
      (node (ref "LED1") (pin "K") (pinfunction "K_K") (pintype "passive"))
      (node (ref "P14") (pin "42") (pinfunction "/LED_WWAN_42") (pintype "passive"))
    )
    (net (code "162") (name "Net-(P14-{slash}PRESET)") (class "Default")
      (node (ref "P14") (pin "22") (pinfunction "/PRESET_22") (pintype "passive"))
      (node (ref "R74") (pin "1") (pinfunction "1_1") (pintype "passive"))
    )
    (net (code "163") (name "Net-(P14-{slash}W_DISABLE)") (class "Default")
      (node (ref "P14") (pin "20") (pinfunction "/W_DISABLE_20") (pintype "passive"))
      (node (ref "R73") (pin "1") (pinfunction "1_1") (pintype "passive"))
    )
    (net (code "164") (name "Net-(Q1-G)") (class "Default")
      (node (ref "C10") (pin "1") (pinfunction "1_1") (pintype "passive"))
      (node (ref "Q1") (pin "1") (pinfunction "G_1") (pintype "passive"))
      (node (ref "Q2") (pin "3") (pinfunction "C_3") (pintype "passive"))
      (node (ref "R6") (pin "1") (pinfunction "1_1") (pintype "passive"))
    )
    (net (code "165") (name "Net-(Q2-B)") (class "Default")
      (node (ref "Q2") (pin "2") (pinfunction "B_2") (pintype "passive"))
      (node (ref "R15") (pin "2") (pinfunction "2_2") (pintype "passive"))
      (node (ref "R20") (pin "2") (pinfunction "2_2") (pintype "passive"))
    )
    (net (code "166") (name "Net-(R65-Pad1)") (class "Default")
      (node (ref "R65") (pin "1") (pinfunction "1_1") (pintype "passive"))
      (node (ref "R72") (pin "2") (pinfunction "2_2") (pintype "passive"))
      (node (ref "SW1") (pin "1") (pinfunction "1_1") (pintype "passive"))
      (node (ref "SW1") (pin "4") (pinfunction "4_4") (pintype "passive"))
    )
    (net (code "167") (name "Net-(R67-Pad1)") (class "Default")
      (node (ref "R67") (pin "1") (pinfunction "1_1") (pintype "passive"))
      (node (ref "R76") (pin "2") (pinfunction "2_2") (pintype "passive"))
      (node (ref "SW2") (pin "1") (pinfunction "1_1") (pintype "passive"))
      (node (ref "SW2") (pin "4") (pinfunction "4_4") (pintype "passive"))
    )
    (net (code "168") (name "Net-(R69-Pad1)") (class "Default")
      (node (ref "R69") (pin "1") (pinfunction "1_1") (pintype "passive"))
      (node (ref "R78") (pin "2") (pinfunction "2_2") (pintype "passive"))
      (node (ref "SW3") (pin "1") (pinfunction "1_1") (pintype "passive"))
      (node (ref "SW3") (pin "4") (pinfunction "4_4") (pintype "passive"))
    )
    (net (code "169") (name "Net-(R71-Pad1)") (class "Default")
      (node (ref "R71") (pin "1") (pinfunction "1_1") (pintype "passive"))
      (node (ref "R79") (pin "2") (pinfunction "2_2") (pintype "passive"))
      (node (ref "SW4") (pin "1") (pinfunction "1_1") (pintype "passive"))
      (node (ref "SW4") (pin "4") (pinfunction "4_4") (pintype "passive"))
    )
    (net (code "170") (name "Net-(R85-Pad2)") (class "Default")
      (node (ref "R85") (pin "2") (pinfunction "2_2") (pintype "passive"))
      (node (ref "SW6") (pin "1") (pinfunction "1_1") (pintype "passive"))
      (node (ref "SW6") (pin "4") (pinfunction "4_4") (pintype "passive"))
    )
    (net (code "171") (name "Net-(U3-C1+)") (class "Default")
      (node (ref "C7") (pin "2") (pinfunction "2_2") (pintype "passive"))
      (node (ref "U3") (pin "1") (pinfunction "C1+_1") (pintype "passive"))
    )
    (net (code "172") (name "Net-(U3-C1-)") (class "Default")
      (node (ref "C7") (pin "1") (pinfunction "1_1") (pintype "passive"))
      (node (ref "U3") (pin "3") (pinfunction "C1-_3") (pintype "passive"))
    )
    (net (code "173") (name "Net-(U3-C2+)") (class "Default")
      (node (ref "C11") (pin "1") (pinfunction "1_1") (pintype "passive"))
      (node (ref "U3") (pin "4") (pinfunction "C2+_4") (pintype "passive"))
    )
    (net (code "174") (name "Net-(U3-C2-)") (class "Default")
      (node (ref "C11") (pin "2") (pinfunction "2_2") (pintype "passive"))
      (node (ref "U3") (pin "5") (pinfunction "C2-_5") (pintype "passive"))
    )
    (net (code "175") (name "Net-(U3-VDD)") (class "Default")
      (node (ref "C8") (pin "1") (pinfunction "1_1") (pintype "passive"))
      (node (ref "U3") (pin "2") (pinfunction "VDD_2") (pintype "power_in"))
    )
    (net (code "176") (name "Net-(U3-VEE)") (class "Default")
      (node (ref "C15") (pin "1") (pinfunction "1_1") (pintype "passive"))
      (node (ref "U3") (pin "6") (pinfunction "VEE_6") (pintype "power_in"))
    )
    (net (code "177") (name "Net-(U4-EN)") (class "Default")
      (node (ref "R7") (pin "1") (pinfunction "1_1") (pintype "passive"))
      (node (ref "U4") (pin "4") (pinfunction "EN_4") (pintype "passive"))
    )
    (net (code "178") (name "Net-(U4-FB)") (class "Default")
      (node (ref "R10") (pin "1") (pinfunction "1_1") (pintype "passive"))
      (node (ref "R17") (pin "2") (pinfunction "2_2") (pintype "passive"))
      (node (ref "U4") (pin "3") (pinfunction "FB_3") (pintype "passive"))
    )
    (net (code "179") (name "Net-(U4-SW)") (class "Default")
      (node (ref "L1") (pin "2") (pinfunction "2_2") (pintype "passive"))
      (node (ref "U4") (pin "1") (pinfunction "SW_1") (pintype "passive"))
      (node (ref "VD3") (pin "A") (pinfunction "A_A") (pintype "passive"))
    )
    (net (code "180") (name "Net-(U5-C1+)") (class "Default")
      (node (ref "C16") (pin "2") (pinfunction "2_2") (pintype "passive"))
      (node (ref "U5") (pin "1") (pinfunction "C1+_1") (pintype "passive"))
    )
    (net (code "181") (name "Net-(U5-C1-)") (class "Default")
      (node (ref "C16") (pin "1") (pinfunction "1_1") (pintype "passive"))
      (node (ref "U5") (pin "3") (pinfunction "C1-_3") (pintype "passive"))
    )
    (net (code "182") (name "Net-(U5-C2+)") (class "Default")
      (node (ref "C19") (pin "1") (pinfunction "1_1") (pintype "passive"))
      (node (ref "U5") (pin "4") (pinfunction "C2+_4") (pintype "passive"))
    )
    (net (code "183") (name "Net-(U5-C2-)") (class "Default")
      (node (ref "C19") (pin "2") (pinfunction "2_2") (pintype "passive"))
      (node (ref "U5") (pin "5") (pinfunction "C2-_5") (pintype "passive"))
    )
    (net (code "184") (name "Net-(U5-VDD)") (class "Default")
      (node (ref "C17") (pin "1") (pinfunction "1_1") (pintype "passive"))
      (node (ref "U5") (pin "2") (pinfunction "VDD_2") (pintype "power_in"))
    )
    (net (code "185") (name "Net-(U5-VEE)") (class "Default")
      (node (ref "C22") (pin "1") (pinfunction "1_1") (pintype "passive"))
      (node (ref "U5") (pin "6") (pinfunction "VEE_6") (pintype "power_in"))
    )
    (net (code "186") (name "Net-(U6-*OVCUR1)") (class "Default")
      (node (ref "R33") (pin "1") (pinfunction "1_1") (pintype "passive"))
      (node (ref "R34") (pin "1") (pinfunction "1_1") (pintype "passive"))
      (node (ref "U6") (pin "21") (pinfunction "*OVCUR1_21") (pintype "input"))
    )
    (net (code "187") (name "Net-(U6-*RESET)") (class "Default")
      (node (ref "C23") (pin "2") (pinfunction "2_2") (pintype "passive"))
      (node (ref "R36") (pin "1") (pinfunction "1_1") (pintype "passive"))
      (node (ref "R42") (pin "2") (pinfunction "2_2") (pintype "passive"))
      (node (ref "U6") (pin "13") (pinfunction "*RESET_13") (pintype "input"))
    )
    (net (code "188") (name "Net-(U6-PGANG)") (class "Default")
      (node (ref "R37") (pin "2") (pinfunction "2_2") (pintype "passive"))
      (node (ref "U6") (pin "18") (pinfunction "PGANG_18") (pintype "bidirectional"))
    )
    (net (code "189") (name "Net-(U6-PSELF)") (class "Default")
      (node (ref "R39") (pin "1") (pinfunction "1_1") (pintype "passive"))
      (node (ref "U6") (pin "17") (pinfunction "PSELF_17") (pintype "input"))
    )
    (net (code "190") (name "Net-(U6-RREF)") (class "Default")
      (node (ref "R32") (pin "2") (pinfunction "2_2") (pintype "passive"))
      (node (ref "U6") (pin "4") (pinfunction "RREF_4") (pintype "bidirectional"))
    )
    (net (code "191") (name "Net-(U7-EN)") (class "Default")
      (node (ref "R56") (pin "2") (pinfunction "2_2") (pintype "passive"))
      (node (ref "R58") (pin "2") (pinfunction "2_2") (pintype "passive"))
      (node (ref "U7") (pin "8") (pinfunction "EN_8") (pintype "passive"))
    )
    (net (code "192") (name "Net-(U7-FB)") (class "Default")
      (node (ref "R57") (pin "1") (pinfunction "1_1") (pintype "passive"))
      (node (ref "R59") (pin "2") (pinfunction "2_2") (pintype "passive"))
      (node (ref "U7") (pin "7") (pinfunction "FB_7") (pintype "passive"))
    )
    (net (code "193") (name "Net-(U7-SW)") (class "Default")
      (node (ref "L2") (pin "1") (pinfunction "1_1") (pintype "passive"))
      (node (ref "U7") (pin "3") (pinfunction "SW_3") (pintype "passive"))
    )
    (net (code "194") (name "Net-(U8-AUXL)") (class "Default")
      (node (ref "C60") (pin "1") (pinfunction "1_1") (pintype "passive"))
      (node (ref "U8") (pin "19") (pinfunction "AUXL_19") (pintype "passive"))
    )
    (net (code "195") (name "Net-(U8-AUXR)") (class "Default")
      (node (ref "C61") (pin "1") (pinfunction "1_1") (pintype "passive"))
      (node (ref "U8") (pin "20") (pinfunction "AUXR_20") (pintype "passive"))
    )
    (net (code "196") (name "Net-(U8-AVDD)") (class "Default")
      (node (ref "R75") (pin "2") (pinfunction "2_2") (pintype "passive"))
      (node (ref "U8") (pin "31") (pinfunction "AVDD_31") (pintype "passive"))
    )
    (net (code "197") (name "Net-(U8-LIN)") (class "Default")
      (node (ref "C57") (pin "2") (pinfunction "2_2") (pintype "passive"))
      (node (ref "U8") (pin "2") (pinfunction "LIN_2") (pintype "passive"))
    )
    (net (code "198") (name "Net-(U8-LIP)") (class "Default")
      (node (ref "C55") (pin "2") (pinfunction "2_2") (pintype "passive"))
      (node (ref "U8") (pin "1") (pinfunction "LIP_1") (pintype "passive"))
    )
    (net (code "199") (name "Net-(U8-LOUT2)") (class "Default")
      (node (ref "P15") (pin "2") (pinfunction "2_2") (pintype "passive"))
      (node (ref "U8") (pin "25") (pinfunction "LOUT2_25") (pintype "passive"))
    )
    (net (code "200") (name "Net-(U8-MODE)") (class "Default")
      (node (ref "R89") (pin "1") (pinfunction "1_1") (pintype "passive"))
      (node (ref "U8") (pin "18") (pinfunction "MODE_18") (pintype "passive"))
    )
    (net (code "201") (name "Net-(U8-ROUT2)") (class "Default")
      (node (ref "P15") (pin "1") (pinfunction "1_1") (pintype "passive"))
      (node (ref "U8") (pin "23") (pinfunction "ROUT2_23") (pintype "passive"))
    )
    (net (code "202") (name "Net-(U8-SCLK)") (class "Default")
      (node (ref "R88") (pin "2") (pinfunction "2_2") (pintype "passive"))
      (node (ref "U8") (pin "16") (pinfunction "SCLK_16") (pintype "passive"))
    )
    (net (code "203") (name "Net-(U8-SDIN)") (class "Default")
      (node (ref "R90") (pin "2") (pinfunction "2_2") (pintype "passive"))
      (node (ref "U8") (pin "17") (pinfunction "SDIN_17") (pintype "passive"))
    )
    (net (code "204") (name "Net-(U8-VMID)") (class "Default")
      (node (ref "C50") (pin "1") (pinfunction "1_1") (pintype "passive"))
      (node (ref "C51") (pin "2") (pinfunction "2_2") (pintype "passive"))
      (node (ref "U8") (pin "27") (pinfunction "VMID_27") (pintype "passive"))
    )
    (net (code "205") (name "Net-(U9-EN)") (class "Default")
      (node (ref "R83") (pin "2") (pinfunction "2_2") (pintype "passive"))
      (node (ref "R86") (pin "2") (pinfunction "2_2") (pintype "passive"))
      (node (ref "U9") (pin "4") (pinfunction "EN_4") (pintype "passive"))
    )
    (net (code "206") (name "Net-(U9-GND)") (class "Default")
      (node (ref "R84") (pin "2") (pinfunction "2_2") (pintype "passive"))
      (node (ref "U9") (pin "2") (pinfunction "GND_2") (pintype "passive"))
    )
    (net (code "207") (name "VBAT-SYS") (class "Default")
      (node (ref "C10") (pin "2") (pinfunction "2_2") (pintype "passive"))
      (node (ref "C32") (pin "2") (pinfunction "2_2") (pintype "passive"))
      (node (ref "C36") (pin "2") (pinfunction "2_2") (pintype "passive"))
      (node (ref "Q1") (pin "2") (pinfunction "S_2") (pintype "passive"))
      (node (ref "R6") (pin "2") (pinfunction "2_2") (pintype "passive"))
      (node (ref "U7") (pin "2") (pinfunction "VIN_2") (pintype "passive"))
    )
    (net (code "208") (name "VBAT-USB") (class "Default")
      (node (ref "C13") (pin "2") (pinfunction "2_2") (pintype "passive"))
      (node (ref "C14") (pin "2") (pinfunction "2_2") (pintype "passive"))
      (node (ref "C28") (pin "2") (pinfunction "2_2") (pintype "passive"))
      (node (ref "C30") (pin "2") (pinfunction "2_2") (pintype "passive"))
      (node (ref "C54") (pin "1") (pinfunction "1_1") (pintype "passive"))
      (node (ref "P11") (pin "17") (pinfunction "17_17") (pintype "passive"))
      (node (ref "P3") (pin "1") (pinfunction "VBUS_1") (pintype "passive"))
      (node (ref "P4") (pin "1") (pinfunction "VBUS_1") (pintype "passive"))
      (node (ref "R10") (pin "2") (pinfunction "2_2") (pintype "passive"))
      (node (ref "R33") (pin "2") (pinfunction "2_2") (pintype "passive"))
      (node (ref "R36") (pin "2") (pinfunction "2_2") (pintype "passive"))
      (node (ref "R39") (pin "2") (pinfunction "2_2") (pintype "passive"))
      (node (ref "U6") (pin "23") (pinfunction "V5_23") (pintype "power_in"))
      (node (ref "U9") (pin "5") (pinfunction "IN_5") (pintype "passive"))
      (node (ref "VD3") (pin "K") (pinfunction "K_K") (pintype "passive"))
    )
    (net (code "209") (name "VCC3P3-SYS") (class "Default")
      (node (ref "C15") (pin "2") (pinfunction "2_2") (pintype "passive"))
      (node (ref "C17") (pin "2") (pinfunction "2_2") (pintype "passive"))
      (node (ref "C18") (pin "1") (pinfunction "1_1") (pintype "passive"))
      (node (ref "C22") (pin "2") (pinfunction "2_2") (pintype "passive"))
      (node (ref "C33") (pin "2") (pinfunction "2_2") (pintype "passive"))
      (node (ref "C34") (pin "2") (pinfunction "2_2") (pintype "passive"))
      (node (ref "C46") (pin "2") (pinfunction "2_2") (pintype "passive"))
      (node (ref "C48") (pin "2") (pinfunction "2_2") (pintype "passive"))
      (node (ref "C8") (pin "2") (pinfunction "2_2") (pintype "passive"))
      (node (ref "C9") (pin "1") (pinfunction "1_1") (pintype "passive"))
      (node (ref "LED2") (pin "A") (pinfunction "A_A") (pintype "passive"))
      (node (ref "LED3") (pin "A") (pinfunction "A_A") (pintype "passive"))
      (node (ref "LED6") (pin "A") (pinfunction "A_A") (pintype "passive"))
      (node (ref "P12") (pin "4") (pinfunction "VDD_4") (pintype "passive"))
      (node (ref "P2") (pin "4") (pinfunction "4_4") (pintype "passive"))
      (node (ref "R15") (pin "1") (pinfunction "1_1") (pintype "passive"))
      (node (ref "R50") (pin "2") (pinfunction "2_2") (pintype "passive"))
      (node (ref "R51") (pin "2") (pinfunction "2_2") (pintype "passive"))
      (node (ref "R52") (pin "2") (pinfunction "2_2") (pintype "passive"))
      (node (ref "R53") (pin "2") (pinfunction "2_2") (pintype "passive"))
      (node (ref "R54") (pin "2") (pinfunction "2_2") (pintype "passive"))
      (node (ref "R55") (pin "2") (pinfunction "2_2") (pintype "passive"))
      (node (ref "R56") (pin "1") (pinfunction "1_1") (pintype "passive"))
      (node (ref "R72") (pin "1") (pinfunction "1_1") (pintype "passive"))
      (node (ref "R75") (pin "1") (pinfunction "1_1") (pintype "passive"))
      (node (ref "R76") (pin "1") (pinfunction "1_1") (pintype "passive"))
      (node (ref "R78") (pin "1") (pinfunction "1_1") (pintype "passive"))
      (node (ref "R79") (pin "1") (pinfunction "1_1") (pintype "passive"))
      (node (ref "U3") (pin "16") (pinfunction "VCC_16") (pintype "power_in"))
      (node (ref "U5") (pin "16") (pinfunction "VCC_16") (pintype "power_in"))
      (node (ref "U8") (pin "13") (pinfunction "DCVDD_13") (pintype "passive"))
      (node (ref "U8") (pin "14") (pinfunction "DBVDD_14") (pintype "passive"))
    )
    (net (code "210") (name "VDD-3G") (class "Default")
      (node (ref "C37") (pin "2") (pinfunction "2_2") (pintype "passive"))
      (node (ref "C38") (pin "2") (pinfunction "2_2") (pintype "passive"))
      (node (ref "C39") (pin "2") (pinfunction "2_2") (pintype "passive"))
      (node (ref "C40") (pin "2") (pinfunction "2_2") (pintype "passive"))
      (node (ref "C41") (pin "2") (pinfunction "2_2") (pintype "passive"))
      (node (ref "C43") (pin "2") (pinfunction "2_2") (pintype "passive"))
      (node (ref "L2") (pin "2") (pinfunction "2_2") (pintype "passive"))
      (node (ref "LED1") (pin "A") (pinfunction "A_A") (pintype "passive"))
      (node (ref "P14") (pin "2") (pinfunction "VDD1_2") (pintype "passive"))
      (node (ref "P14") (pin "24") (pinfunction "VDD2_24") (pintype "passive"))
      (node (ref "P14") (pin "39") (pinfunction "VDD3_39") (pintype "passive"))
      (node (ref "P14") (pin "41") (pinfunction "VDD4_41") (pintype "passive"))
      (node (ref "P14") (pin "52") (pinfunction "VDD5_52") (pintype "passive"))
      (node (ref "R57") (pin "2") (pinfunction "2_2") (pintype "passive"))
      (node (ref "R73") (pin "2") (pinfunction "2_2") (pintype "passive"))
      (node (ref "R74") (pin "2") (pinfunction "2_2") (pintype "passive"))
      (node (ref "U7") (pin "5") (pinfunction "OUT_5") (pintype "passive"))
    )
    (net (code "211") (name "unconnected-(P2-Pad35)") (class "Default")
      (node (ref "P2") (pin "35") (pinfunction "35_35") (pintype "passive+no_connect"))
    )
    (net (code "212") (name "unconnected-(P4-Pad7)") (class "Default")
      (node (ref "P4") (pin "7") (pinfunction "7_7") (pintype "passive"))
    )
    (net (code "213") (name "unconnected-(P4-Pad8)") (class "Default")
      (node (ref "P4") (pin "8") (pinfunction "8_8") (pintype "passive"))
    )
    (net (code "214") (name "unconnected-(P10-Pad2)") (class "Default")
      (node (ref "P10") (pin "2") (pinfunction "2_2") (pintype "passive"))
    )
    (net (code "215") (name "unconnected-(P11-Pad13)") (class "Default")
      (node (ref "P11") (pin "13") (pinfunction "13_13") (pintype "passive"))
    )
    (net (code "216") (name "unconnected-(P11-Pad14)") (class "Default")
      (node (ref "P11") (pin "14") (pinfunction "14_14") (pintype "passive"))
    )
    (net (code "217") (name "unconnected-(P11-Pad15)") (class "Default")
      (node (ref "P11") (pin "15") (pinfunction "15_15") (pintype "passive"))
    )
    (net (code "218") (name "unconnected-(P11-Pad16)") (class "Default")
      (node (ref "P11") (pin "16") (pinfunction "16_16") (pintype "passive"))
    )
    (net (code "219") (name "unconnected-(P13-NC-Pad4)") (class "Default")
      (node (ref "P13") (pin "4") (pinfunction "NC_4") (pintype "passive+no_connect"))
    )
    (net (code "220") (name "unconnected-(P13-NC-Pad8)") (class "Default")
      (node (ref "P13") (pin "8") (pinfunction "NC_8") (pintype "passive+no_connect"))
    )
    (net (code "221") (name "unconnected-(P14-GND9-Pad34)") (class "Default")
      (node (ref "P14") (pin "34") (pinfunction "GND9_34") (pintype "passive"))
    )
    (net (code "222") (name "unconnected-(P14-M-Pad0)") (class "Default")
      (node (ref "P14") (pin "0") (pinfunction "M_0") (pintype "passive+no_connect"))
    )
    (net (code "223") (name "unconnected-(P14-NC1-Pad1)") (class "Default")
      (node (ref "P14") (pin "1") (pinfunction "NC1_1") (pintype "passive+no_connect"))
    )
    (net (code "224") (name "unconnected-(P14-NC2-Pad3)") (class "Default")
      (node (ref "P14") (pin "3") (pinfunction "NC2_3") (pintype "passive+no_connect"))
    )
    (net (code "225") (name "unconnected-(P14-NC3-Pad5)") (class "Default")
      (node (ref "P14") (pin "5") (pinfunction "NC3_5") (pintype "passive+no_connect"))
    )
    (net (code "226") (name "unconnected-(P14-NC4-Pad6)") (class "Default")
      (node (ref "P14") (pin "6") (pinfunction "NC4_6") (pintype "passive+no_connect"))
    )
    (net (code "227") (name "unconnected-(P14-NC5-Pad7)") (class "Default")
      (node (ref "P14") (pin "7") (pinfunction "NC5_7") (pintype "passive+no_connect"))
    )
    (net (code "228") (name "unconnected-(P14-NC6-Pad11)") (class "Default")
      (node (ref "P14") (pin "11") (pinfunction "NC6_11") (pintype "passive+no_connect"))
    )
    (net (code "229") (name "unconnected-(P14-NC7-Pad13)") (class "Default")
      (node (ref "P14") (pin "13") (pinfunction "NC7_13") (pintype "passive+no_connect"))
    )
    (net (code "230") (name "unconnected-(P14-NC8-Pad16)") (class "Default")
      (node (ref "P14") (pin "16") (pinfunction "NC8_16") (pintype "passive+no_connect"))
    )
    (net (code "231") (name "unconnected-(P14-NC9-Pad17)") (class "Default")
      (node (ref "P14") (pin "17") (pinfunction "NC9_17") (pintype "passive+no_connect"))
    )
    (net (code "232") (name "unconnected-(P14-NC10-Pad19)") (class "Default")
      (node (ref "P14") (pin "19") (pinfunction "NC10_19") (pintype "passive+no_connect"))
    )
    (net (code "233") (name "unconnected-(P14-NC11-Pad23)") (class "Default")
      (node (ref "P14") (pin "23") (pinfunction "NC11_23") (pintype "passive+no_connect"))
    )
    (net (code "234") (name "unconnected-(P14-NC12-Pad25)") (class "Default")
      (node (ref "P14") (pin "25") (pinfunction "NC12_25") (pintype "passive+no_connect"))
    )
    (net (code "235") (name "unconnected-(P14-NC13-Pad28)") (class "Default")
      (node (ref "P14") (pin "28") (pinfunction "NC13_28") (pintype "passive+no_connect"))
    )
    (net (code "236") (name "unconnected-(P14-NC14-Pad30)") (class "Default")
      (node (ref "P14") (pin "30") (pinfunction "NC14_30") (pintype "passive+no_connect"))
    )
    (net (code "237") (name "unconnected-(P14-NC15-Pad31)") (class "Default")
      (node (ref "P14") (pin "31") (pinfunction "NC15_31") (pintype "passive+no_connect"))
    )
    (net (code "238") (name "unconnected-(P14-NC16-Pad32)") (class "Default")
      (node (ref "P14") (pin "32") (pinfunction "NC16_32") (pintype "passive+no_connect"))
    )
    (net (code "239") (name "unconnected-(P14-NC17-Pad33)") (class "Default")
      (node (ref "P14") (pin "33") (pinfunction "NC17_33") (pintype "passive+no_connect"))
    )
    (net (code "240") (name "unconnected-(P14-NC18-Pad45)") (class "Default")
      (node (ref "P14") (pin "45") (pinfunction "NC18_45") (pintype "passive+no_connect"))
    )
    (net (code "241") (name "unconnected-(P14-NC19-Pad46)") (class "Default")
      (node (ref "P14") (pin "46") (pinfunction "NC19_46") (pintype "passive+no_connect"))
    )
    (net (code "242") (name "unconnected-(P14-NC20-Pad47)") (class "Default")
      (node (ref "P14") (pin "47") (pinfunction "NC20_47") (pintype "passive+no_connect"))
    )
    (net (code "243") (name "unconnected-(P14-NC21-Pad48)") (class "Default")
      (node (ref "P14") (pin "48") (pinfunction "NC21_48") (pintype "passive+no_connect"))
    )
    (net (code "244") (name "unconnected-(P14-NC22-Pad49)") (class "Default")
      (node (ref "P14") (pin "49") (pinfunction "NC22_49") (pintype "passive+no_connect"))
    )
    (net (code "245") (name "unconnected-(P14-NC23-Pad51)") (class "Default")
      (node (ref "P14") (pin "51") (pinfunction "NC23_51") (pintype "passive+no_connect"))
    )
    (net (code "246") (name "unconnected-(P14-{slash}LED_WLAN-Pad44)") (class "Default")
      (node (ref "P14") (pin "44") (pinfunction "/LED_WLAN_44") (pintype "passive+no_connect"))
    )
    (net (code "247") (name "unconnected-(U4-FLT-Pad6)") (class "Default")
      (node (ref "U4") (pin "6") (pinfunction "FLT_6") (pintype "passive"))
    )
    (net (code "248") (name "unconnected-(U6-*OVCUR2-Pad19)") (class "Default")
      (node (ref "U6") (pin "19") (pinfunction "*OVCUR2_19") (pintype "input+no_connect"))
    )
    (net (code "249") (name "unconnected-(U6-*PWREN1-Pad22)") (class "Default")
      (node (ref "U6") (pin "22") (pinfunction "*PWREN1_22") (pintype "output+no_connect"))
    )
    (net (code "250") (name "unconnected-(U6-*PWREN2-Pad20)") (class "Default")
      (node (ref "U6") (pin "20") (pinfunction "*PWREN2_20") (pintype "output+no_connect"))
    )
    (net (code "251") (name "unconnected-(U6-TEST{slash}SCL-Pad14)") (class "Default")
      (node (ref "U6") (pin "14") (pinfunction "TEST/SCL_14") (pintype "bidirectional+no_connect"))
    )
    (net (code "252") (name "unconnected-(U7-PG-Pad1)") (class "Default")
      (node (ref "U7") (pin "1") (pinfunction "PG_1") (pintype "passive+no_connect"))
    )
    (net (code "253") (name "unconnected-(U8-CSB{slash}GPIO1-Pad15)") (class "Default")
      (node (ref "U8") (pin "15") (pinfunction "CSB/GPIO1_15") (pintype "passive+no_connect"))
    )
    (net (code "254") (name "unconnected-(U8-DNC-Pad4)") (class "Default")
      (node (ref "U8") (pin "4") (pinfunction "DNC_4") (pintype "passive+no_connect"))
    )
    (net (code "255") (name "unconnected-(U8-DNC-Pad5)") (class "Default")
      (node (ref "U8") (pin "5") (pinfunction "DNC_5") (pintype "passive+no_connect"))
    )
    (net (code "256") (name "unconnected-(U8-DNC-Pad6)") (class "Default")
      (node (ref "U8") (pin "6") (pinfunction "DNC_6") (pintype "passive+no_connect"))
    )
    (net (code "257") (name "unconnected-(U8-L2{slash}GPIO2-Pad3)") (class "Default")
      (node (ref "U8") (pin "3") (pinfunction "L2/GPIO2_3") (pintype "passive+no_connect"))
    )
    (net (code "258") (name "unconnected-(U8-OUT3-Pad22)") (class "Default")
      (node (ref "U8") (pin "22") (pinfunction "OUT3_22") (pintype "passive+no_connect"))
    )
    (net (code "259") (name "unconnected-(U8-OUT4-Pad21)") (class "Default")
      (node (ref "U8") (pin "21") (pinfunction "OUT4_21") (pintype "passive+no_connect"))
    )
  )
)
